# module.net
KiCad netlist of a schematic drawn in EAGLE
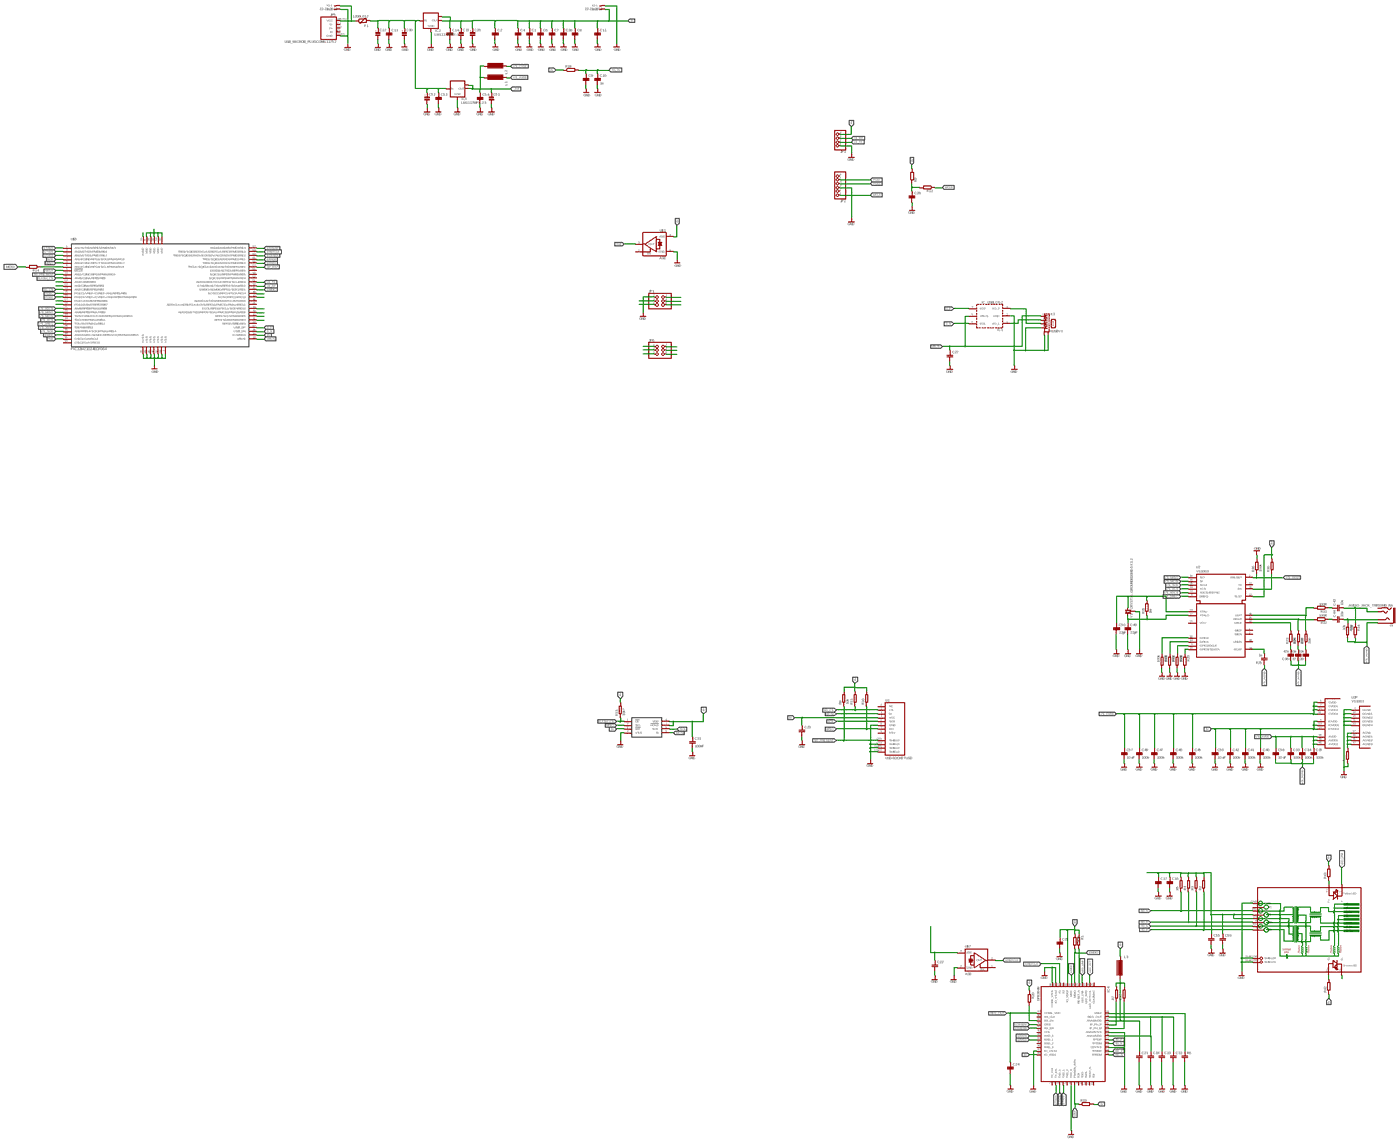
[diagram p0: schematic, sheet 1, overview]
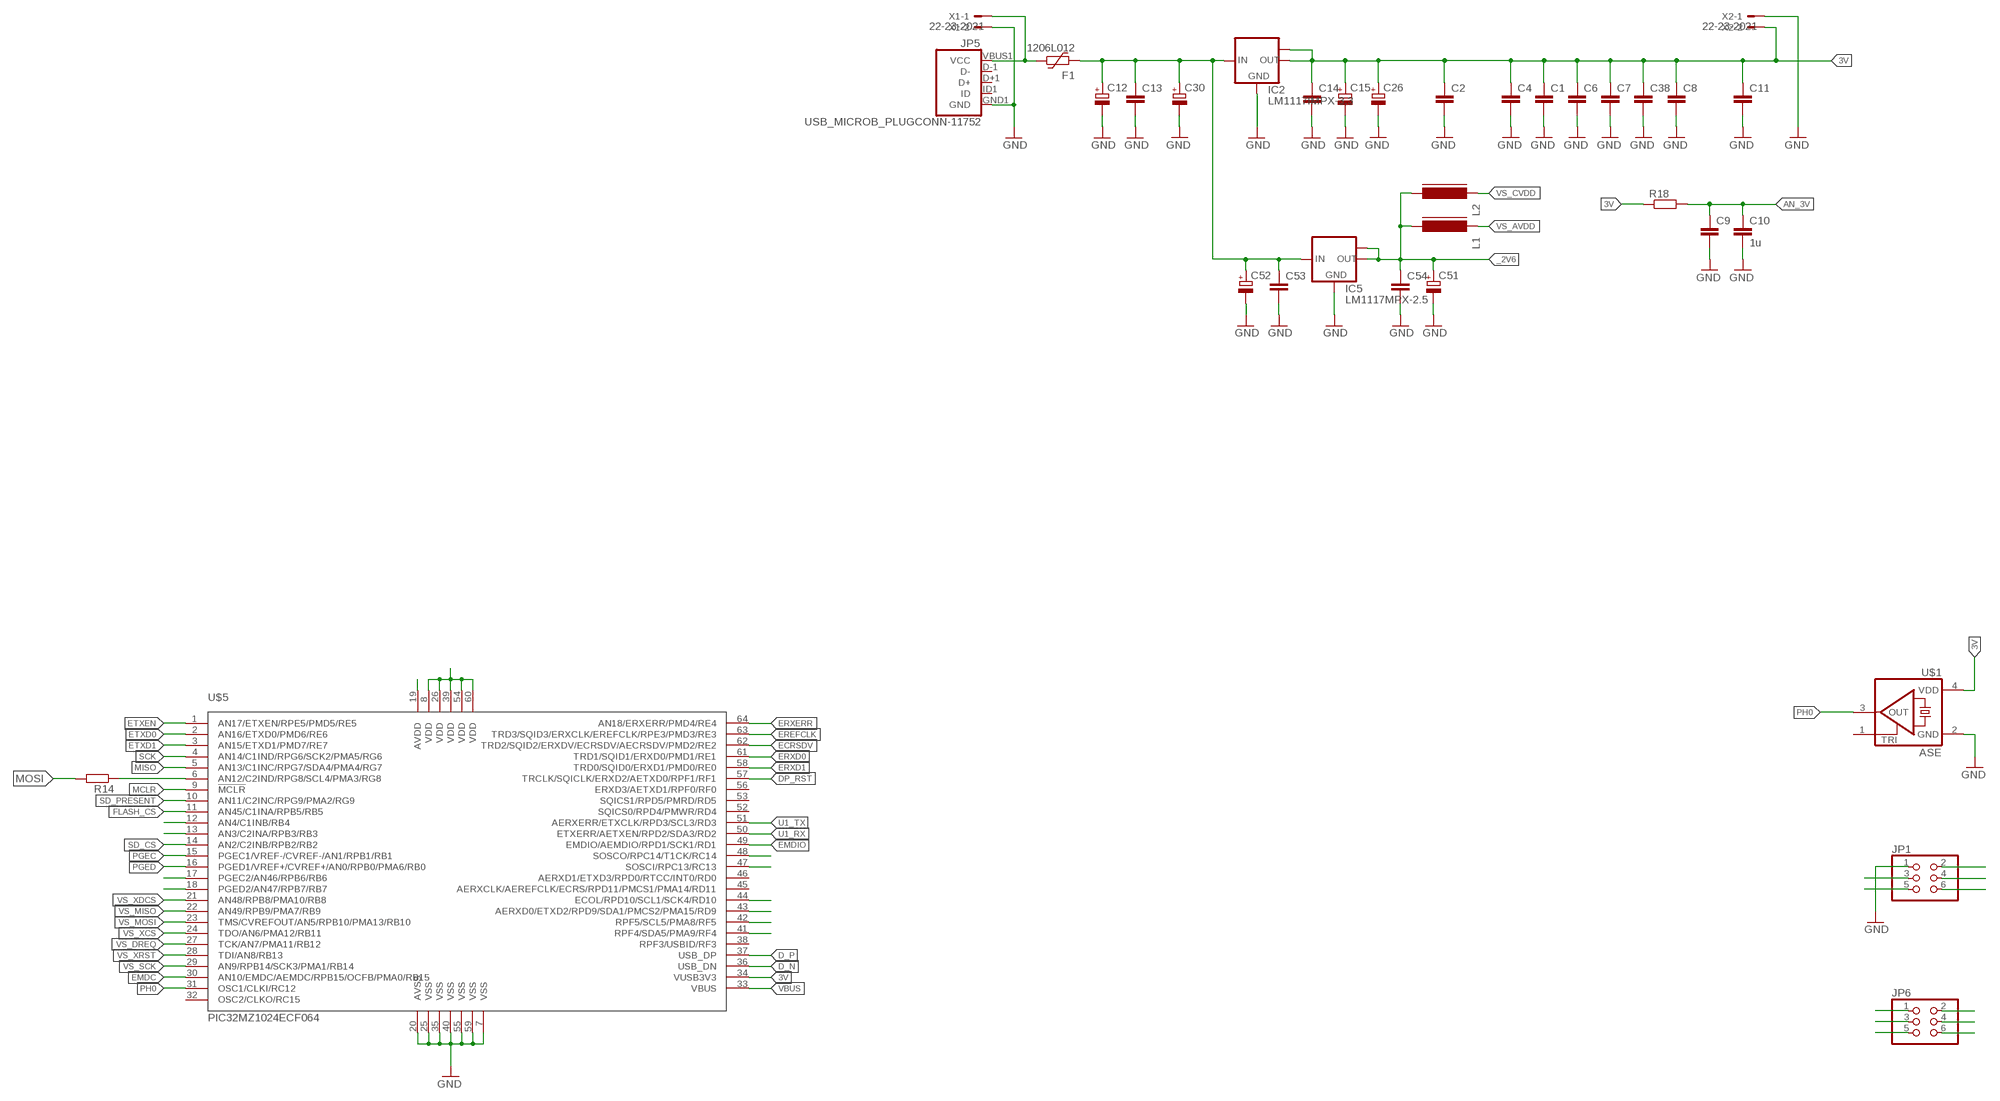
[diagram p1: schematic, sheet 1, part 1 of 4]
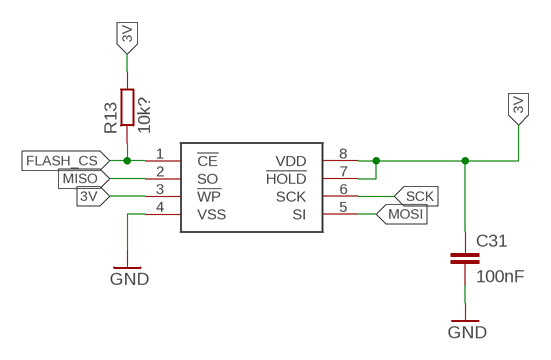
[diagram p2: schematic, sheet 1, part 2 of 4]
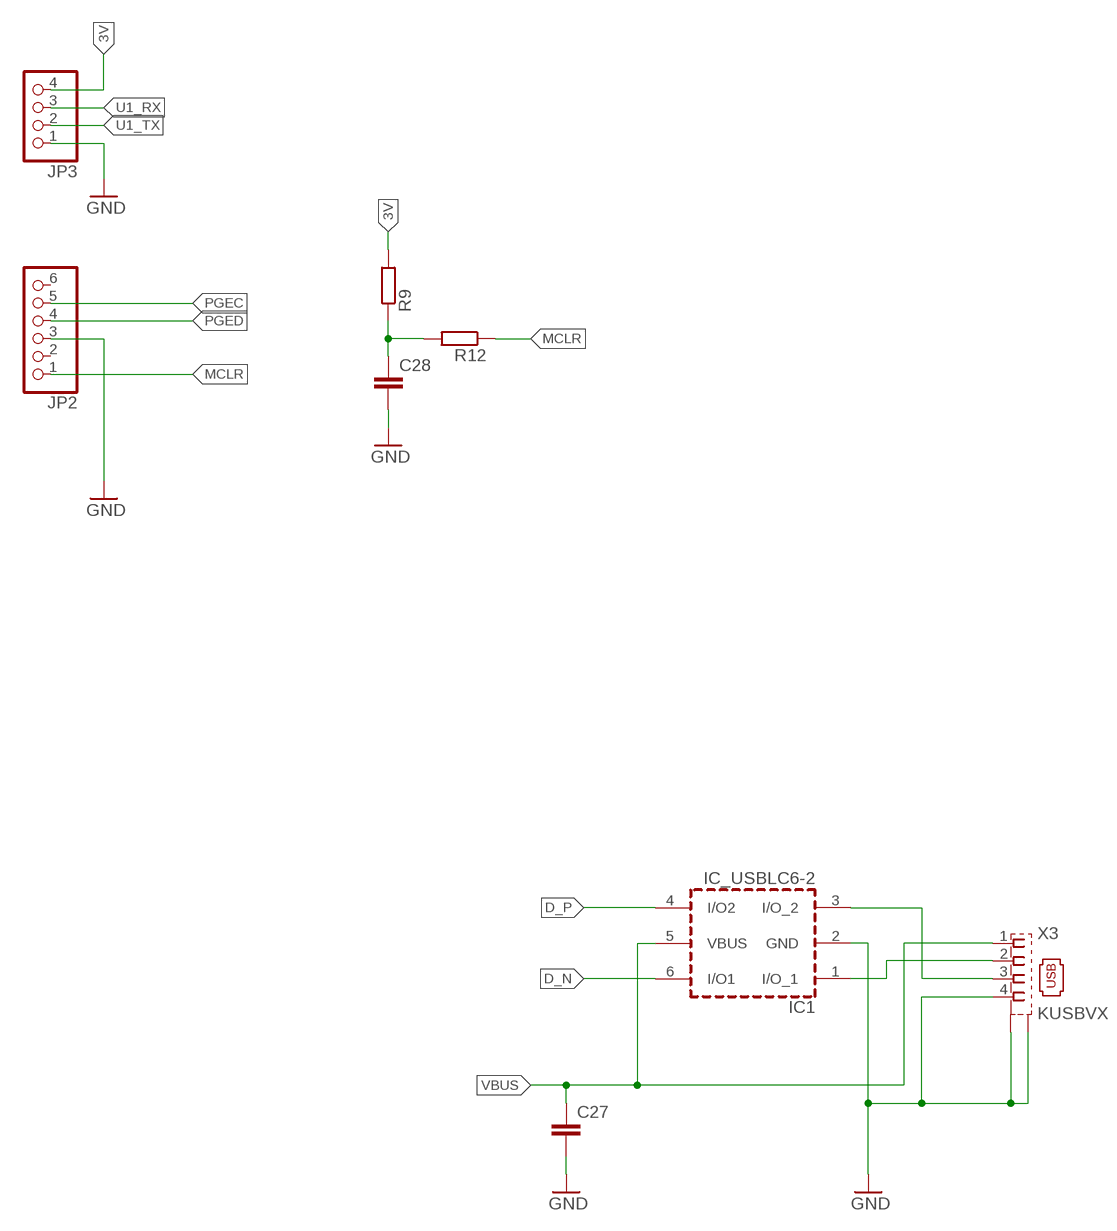
[diagram p3: schematic, sheet 1, part 3 of 4]
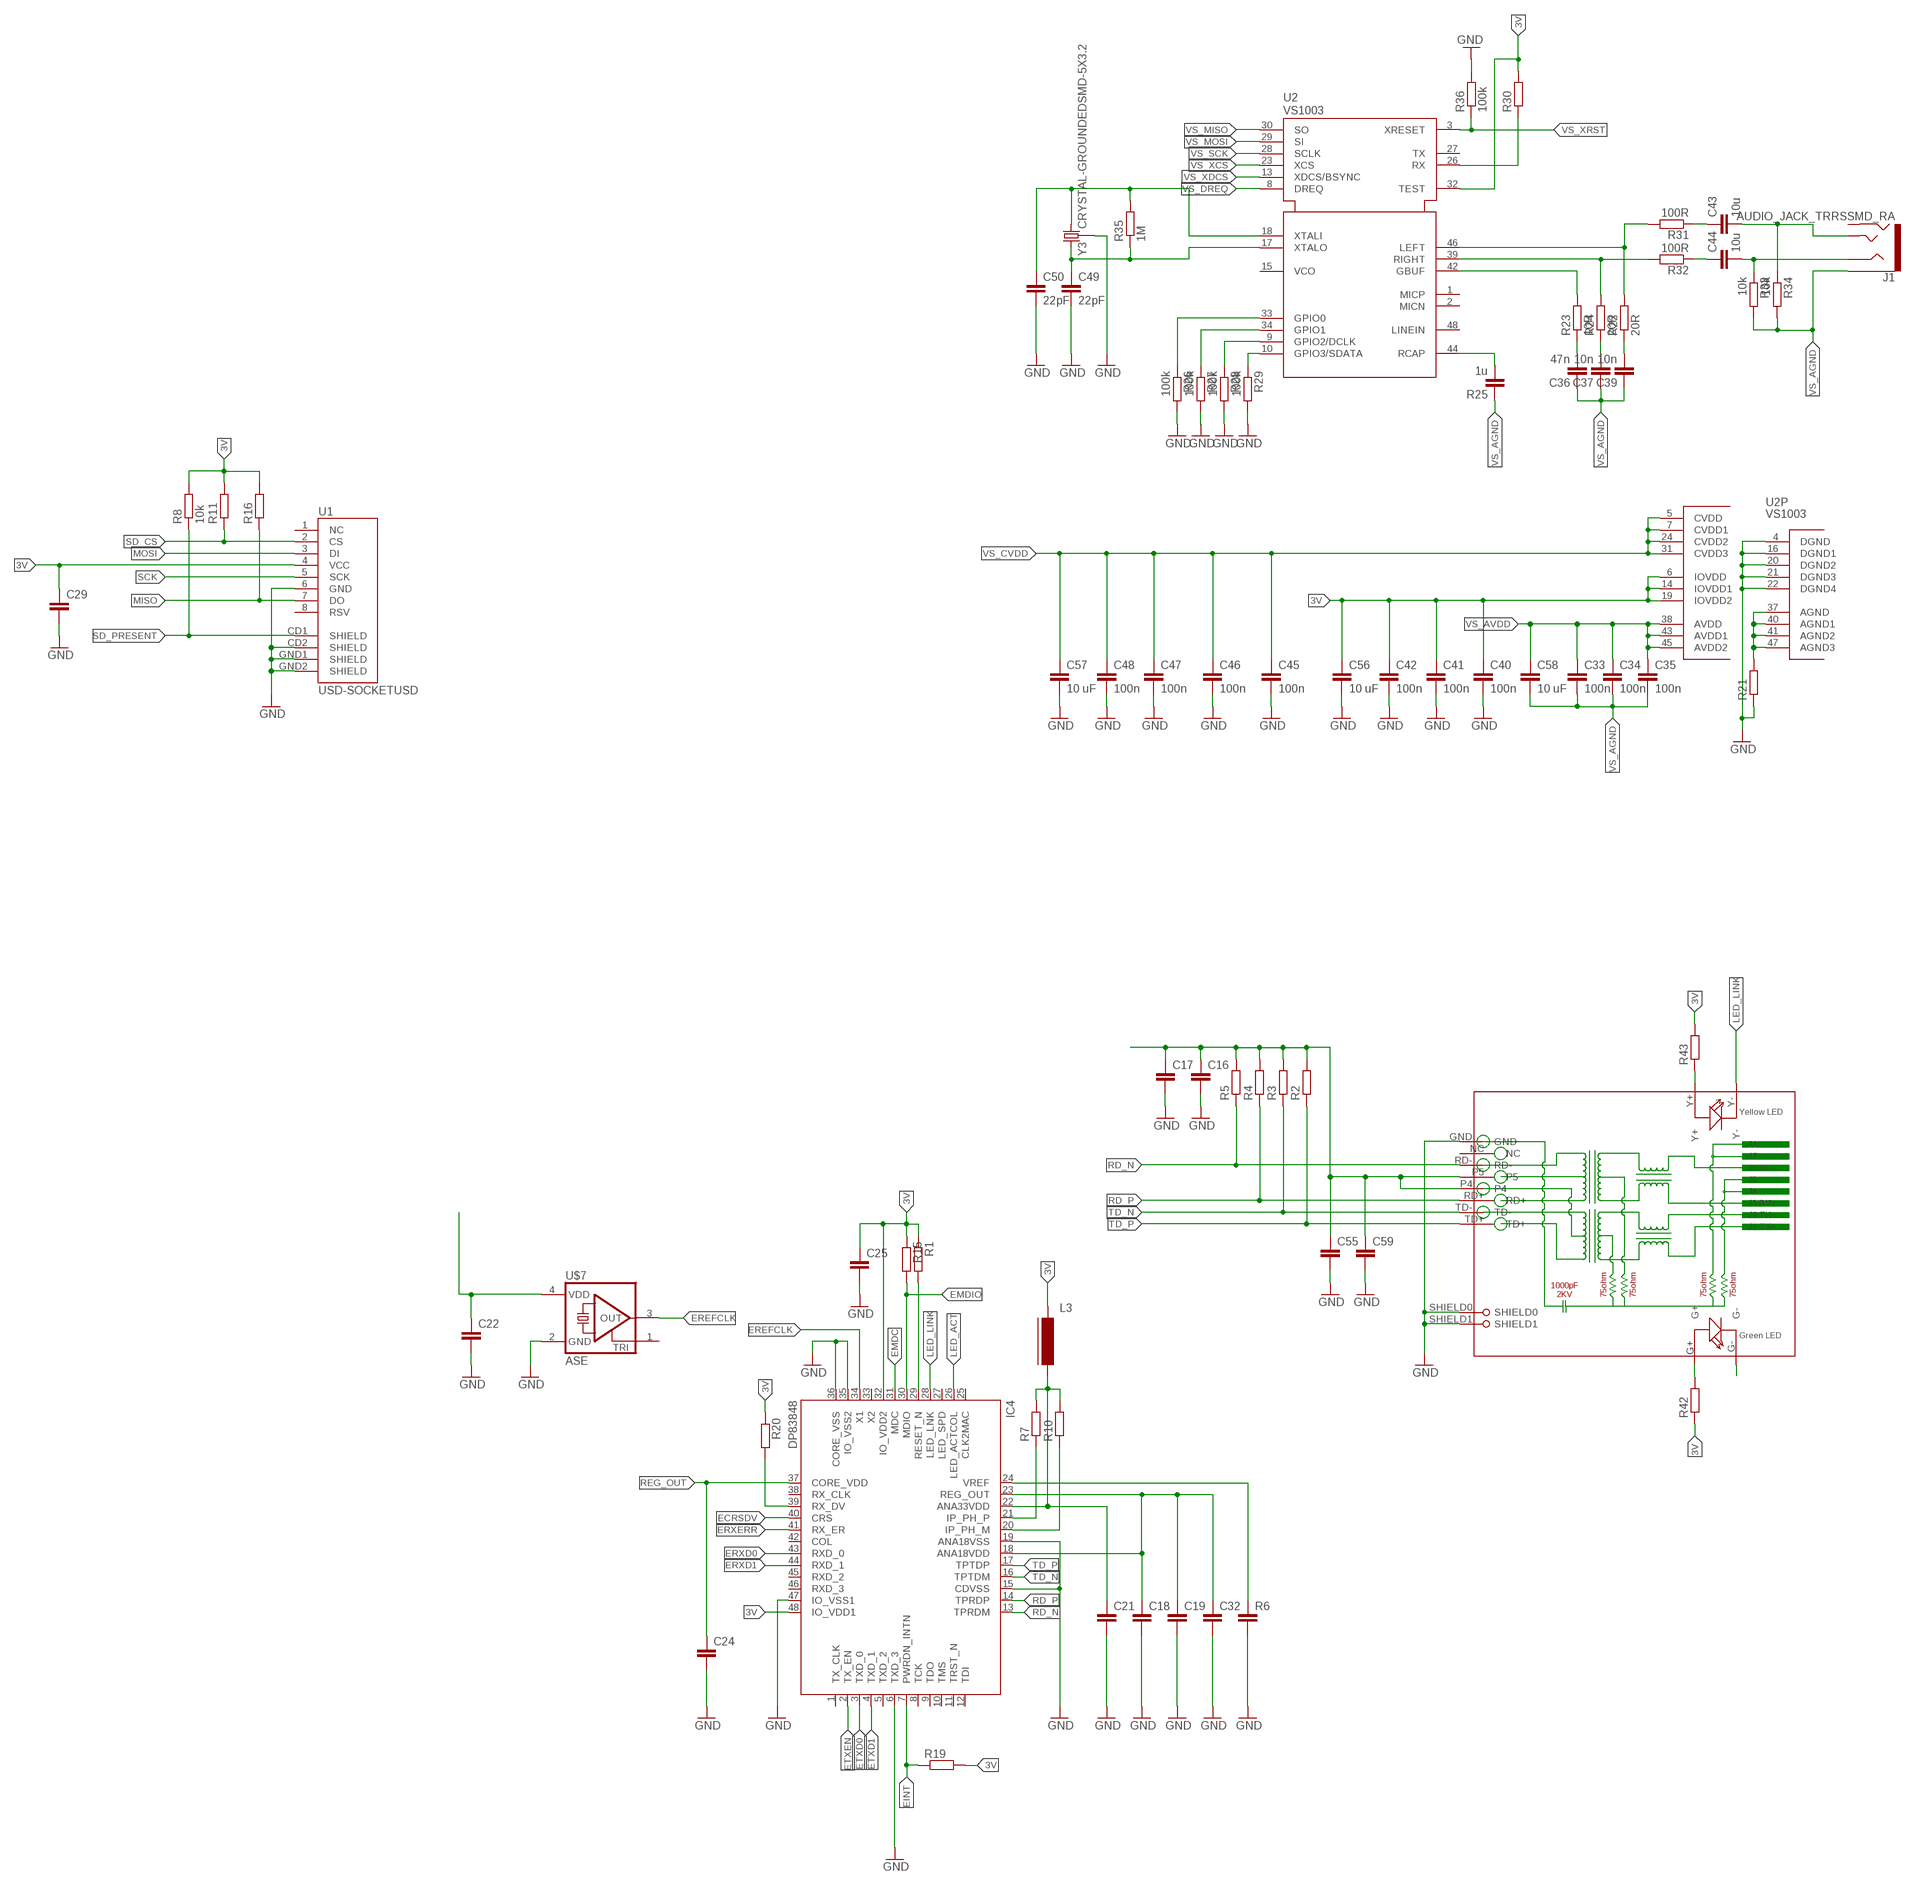
[diagram p4: schematic, sheet 1, part 4 of 4]

(export (version "E")
  (design (tool "Eeschema 10.0.6"))
  (components
    (comp (ref "C1")
      (value "C-EUC0402")
      (footprint "eagle-import:C0402")
      (libsource (lib "eagle-import") (part "C-EUC0402"))
    )
    (comp (ref "C2")
      (value "C-EUC0402")
      (footprint "eagle-import:C0402")
      (libsource (lib "eagle-import") (part "C-EUC0402"))
    )
    (comp (ref "C4")
      (value "C-EUC0402")
      (footprint "eagle-import:C0402")
      (libsource (lib "eagle-import") (part "C-EUC0402"))
    )
    (comp (ref "C6")
      (value "C-EUC0402")
      (footprint "eagle-import:C0402")
      (libsource (lib "eagle-import") (part "C-EUC0402"))
    )
    (comp (ref "C7")
      (value "C-EUC0402")
      (footprint "eagle-import:C0402")
      (libsource (lib "eagle-import") (part "C-EUC0402"))
    )
    (comp (ref "C8")
      (value "C-EUC0402")
      (footprint "eagle-import:C0402")
      (libsource (lib "eagle-import") (part "C-EUC0402"))
    )
    (comp (ref "C9")
      (value "C-EUC0402")
      (footprint "eagle-import:C0402")
      (libsource (lib "eagle-import") (part "C-EUC0402"))
    )
    (comp (ref "C10")
      (value "1u")
      (footprint "eagle-import:C0603")
      (libsource (lib "eagle-import") (part "C-EUC0603"))
    )
    (comp (ref "C11")
      (value "C-EUC0402")
      (footprint "eagle-import:C0402")
      (libsource (lib "eagle-import") (part "C-EUC0402"))
    )
    (comp (ref "C12")
      (value "CPOL-EUSMCB")
      (footprint "eagle-import:SMC_B")
      (libsource (lib "eagle-import") (part "CPOL-EUSMCB"))
    )
    (comp (ref "C13")
      (value "C-EUC0603")
      (footprint "eagle-import:C0603")
      (libsource (lib "eagle-import") (part "C-EUC0603"))
    )
    (comp (ref "C14")
      (value "C-EUC0603")
      (footprint "eagle-import:C0603")
      (libsource (lib "eagle-import") (part "C-EUC0603"))
    )
    (comp (ref "C15")
      (value "CPOL-EUSMCB")
      (footprint "eagle-import:SMC_B")
      (libsource (lib "eagle-import") (part "CPOL-EUSMCB"))
    )
    (comp (ref "C16")
      (value "C-EUC0603")
      (footprint "eagle-import:C0603")
      (libsource (lib "eagle-import") (part "C-EUC0603"))
    )
    (comp (ref "C17")
      (value "C-EUC0603")
      (footprint "eagle-import:C0603")
      (libsource (lib "eagle-import") (part "C-EUC0603"))
    )
    (comp (ref "C18")
      (value "C-EUC0402")
      (footprint "eagle-import:C0402")
      (libsource (lib "eagle-import") (part "C-EUC0402"))
    )
    (comp (ref "C19")
      (value "C-EUC0402")
      (footprint "eagle-import:C0402")
      (libsource (lib "eagle-import") (part "C-EUC0402"))
    )
    (comp (ref "C21")
      (value "C-EUC0402")
      (footprint "eagle-import:C0402")
      (libsource (lib "eagle-import") (part "C-EUC0402"))
    )
    (comp (ref "C22")
      (value "C-EUC0402")
      (footprint "eagle-import:C0402")
      (libsource (lib "eagle-import") (part "C-EUC0402"))
    )
    (comp (ref "C24")
      (value "C-EUC0603")
      (footprint "eagle-import:C0603")
      (libsource (lib "eagle-import") (part "C-EUC0603"))
    )
    (comp (ref "C25")
      (value "C-EUC0603")
      (footprint "eagle-import:C0603")
      (libsource (lib "eagle-import") (part "C-EUC0603"))
    )
    (comp (ref "C26")
      (value "CPOL-EUSMCA")
      (footprint "eagle-import:SMC_A")
      (libsource (lib "eagle-import") (part "CPOL-EUSMCA"))
    )
    (comp (ref "C27")
      (value "C-EUC0603")
      (footprint "eagle-import:C0603")
      (libsource (lib "eagle-import") (part "C-EUC0603"))
    )
    (comp (ref "C28")
      (value "C-EUC0603")
      (footprint "eagle-import:C0603")
      (libsource (lib "eagle-import") (part "C-EUC0603"))
    )
    (comp (ref "C29")
      (value "C-EUC0603")
      (footprint "eagle-import:C0603")
      (libsource (lib "eagle-import") (part "C-EUC0603"))
    )
    (comp (ref "C30")
      (value "CPOL-EUSMCA")
      (footprint "eagle-import:SMC_A")
      (libsource (lib "eagle-import") (part "CPOL-EUSMCA"))
    )
    (comp (ref "C31")
      (value "100nF")
      (footprint "eagle-import:C0603")
      (libsource (lib "eagle-import") (part "C-EUC0603"))
    )
    (comp (ref "C32")
      (value "C-EUC0603")
      (footprint "eagle-import:C0603")
      (libsource (lib "eagle-import") (part "C-EUC0603"))
    )
    (comp (ref "C33")
      (value "100n")
      (footprint "eagle-import:C0603")
      (libsource (lib "eagle-import") (part "C-EUC0603"))
    )
    (comp (ref "C34")
      (value "100n")
      (footprint "eagle-import:C0603")
      (libsource (lib "eagle-import") (part "C-EUC0603"))
    )
    (comp (ref "C35")
      (value "100n")
      (footprint "eagle-import:C0603")
      (libsource (lib "eagle-import") (part "C-EUC0603"))
    )
    (comp (ref "C36")
      (value "47n")
      (footprint "eagle-import:C0603")
      (libsource (lib "eagle-import") (part "C-EUC0603"))
    )
    (comp (ref "C37")
      (value "10n")
      (footprint "eagle-import:C0603")
      (libsource (lib "eagle-import") (part "C-EUC0603"))
    )
    (comp (ref "C38")
      (value "C-EUC0402")
      (footprint "eagle-import:C0402")
      (libsource (lib "eagle-import") (part "C-EUC0402"))
    )
    (comp (ref "C39")
      (value "10n")
      (footprint "eagle-import:C0603")
      (libsource (lib "eagle-import") (part "C-EUC0603"))
    )
    (comp (ref "C40")
      (value "100n")
      (footprint "eagle-import:C0402")
      (libsource (lib "eagle-import") (part "C-EUC0402"))
    )
    (comp (ref "C41")
      (value "100n")
      (footprint "eagle-import:C0402")
      (libsource (lib "eagle-import") (part "C-EUC0402"))
    )
    (comp (ref "C42")
      (value "100n")
      (footprint "eagle-import:C0402")
      (libsource (lib "eagle-import") (part "C-EUC0402"))
    )
    (comp (ref "C43")
      (value "10u")
      (footprint "eagle-import:C0603")
      (libsource (lib "eagle-import") (part "C-EUC0603"))
    )
    (comp (ref "C44")
      (value "10u")
      (footprint "eagle-import:C0603")
      (libsource (lib "eagle-import") (part "C-EUC0603"))
    )
    (comp (ref "C45")
      (value "100n")
      (footprint "eagle-import:C0402")
      (libsource (lib "eagle-import") (part "C-EUC0402"))
    )
    (comp (ref "C46")
      (value "100n")
      (footprint "eagle-import:C0603")
      (libsource (lib "eagle-import") (part "C-EUC0603"))
    )
    (comp (ref "C47")
      (value "100n")
      (footprint "eagle-import:C0603")
      (libsource (lib "eagle-import") (part "C-EUC0603"))
    )
    (comp (ref "C48")
      (value "100n")
      (footprint "eagle-import:C0603")
      (libsource (lib "eagle-import") (part "C-EUC0603"))
    )
    (comp (ref "C49")
      (value "22pF")
      (footprint "eagle-import:C0603")
      (libsource (lib "eagle-import") (part "C-EUC0603"))
    )
    (comp (ref "C50")
      (value "22pF")
      (footprint "eagle-import:C0603")
      (libsource (lib "eagle-import") (part "C-EUC0603"))
    )
    (comp (ref "C51")
      (value "CPOL-EUSMCB")
      (footprint "eagle-import:SMC_B")
      (libsource (lib "eagle-import") (part "CPOL-EUSMCB"))
    )
    (comp (ref "C52")
      (value "CPOL-EUSMCB")
      (footprint "eagle-import:SMC_B")
      (libsource (lib "eagle-import") (part "CPOL-EUSMCB"))
    )
    (comp (ref "C53")
      (value "C-EUC0603")
      (footprint "eagle-import:C0603")
      (libsource (lib "eagle-import") (part "C-EUC0603"))
    )
    (comp (ref "C54")
      (value "C-EUC0603")
      (footprint "eagle-import:C0603")
      (libsource (lib "eagle-import") (part "C-EUC0603"))
    )
    (comp (ref "C55")
      (value "C-EUC0603")
      (footprint "eagle-import:C0603")
      (libsource (lib "eagle-import") (part "C-EUC0603"))
    )
    (comp (ref "C56")
      (value "10 uF")
      (footprint "eagle-import:C0603")
      (libsource (lib "eagle-import") (part "C-EUC0603"))
    )
    (comp (ref "C57")
      (value "10 uF")
      (footprint "eagle-import:C0603")
      (libsource (lib "eagle-import") (part "C-EUC0603"))
    )
    (comp (ref "C58")
      (value "10 uF")
      (footprint "eagle-import:C0603")
      (libsource (lib "eagle-import") (part "C-EUC0603"))
    )
    (comp (ref "C59")
      (value "C-EUC0603")
      (footprint "eagle-import:C0603")
      (libsource (lib "eagle-import") (part "C-EUC0603"))
    )
    (comp (ref "F1")
      (value "1206L012")
      (footprint "eagle-import:1206L")
      (fields (field (name "MF") "Littelfuse"))
      (libsource (lib "eagle-import") (part "?1206L012"))
    )
    (comp (ref "IC1")
      (value "IC_USBLC6-2")
      (footprint "eagle-import:SOT-23-6L")
      (libsource (lib "eagle-import") (part "IC_USBLC6-2"))
    )
    (comp (ref "IC2")
      (value "LM1117IMPX-3.3")
      (footprint "eagle-import:SOT223")
      (libsource (lib "eagle-import") (part "LM1117IMPX-3.3"))
    )
    (comp (ref "IC4")
      (value "DP83848")
      (footprint "eagle-import:LQFP48")
      (fields (field (name "MPN") "DP83848VYB"))
      (libsource (lib "eagle-import") (part "DP83848"))
    )
    (comp (ref "IC5")
      (value "LM1117MPX-2.5")
      (footprint "eagle-import:SOT223")
      (libsource (lib "eagle-import") (part "LM1117MPX-2.5"))
    )
    (comp (ref "J1")
      (value "AUDIO_JACK_TRRSSMD_RA")
      (footprint "eagle-import:AUDIO_JACK_3.5MM_TRRS_SMD_RA")
      (libsource (lib "eagle-import") (part "AUDIO_JACK_TRRSSMD_RA"))
    )
    (comp (ref "JP1")
      (value "PINHD-2X3")
      (footprint "eagle-import:2X03")
      (libsource (lib "eagle-import") (part "PINHD-2X3"))
    )
    (comp (ref "JP2")
      (value "PINHD-1X6")
      (footprint "eagle-import:1X06")
      (libsource (lib "eagle-import") (part "PINHD-1X6"))
    )
    (comp (ref "JP3")
      (value "PINHD-1X4")
      (footprint "eagle-import:1X04")
      (libsource (lib "eagle-import") (part "PINHD-1X4"))
    )
    (comp (ref "JP5")
      (value "USB_MICROB_PLUGCONN-11752")
      (footprint "eagle-import:USB-B-MICRO-SMD_V03")
      (libsource (lib "eagle-import") (part "USB_MICROB_PLUGCONN-11752"))
    )
    (comp (ref "JP6")
      (value "PINHD-2X3")
      (footprint "eagle-import:2X03")
      (libsource (lib "eagle-import") (part "PINHD-2X3"))
    )
    (comp (ref "L1")
      (value "FERRITE-0805")
      (footprint "eagle-import:FB805")
      (libsource (lib "eagle-import") (part "FERRITE-0805"))
    )
    (comp (ref "L2")
      (value "FERRITE-0805")
      (footprint "eagle-import:FB805")
      (libsource (lib "eagle-import") (part "FERRITE-0805"))
    )
    (comp (ref "L3")
      (value "FERRITE-0805")
      (footprint "eagle-import:FB805")
      (libsource (lib "eagle-import") (part "FERRITE-0805"))
    )
    (comp (ref "R1")
      (value "R-EU_R0402")
      (footprint "eagle-import:R0402")
      (libsource (lib "eagle-import") (part "R-EU_R0402"))
    )
    (comp (ref "R2")
      (value "R-EU_R0603")
      (footprint "eagle-import:R0603")
      (libsource (lib "eagle-import") (part "R-EU_R0603"))
    )
    (comp (ref "R3")
      (value "R-EU_R0603")
      (footprint "eagle-import:R0603")
      (libsource (lib "eagle-import") (part "R-EU_R0603"))
    )
    (comp (ref "R4")
      (value "R-EU_R0603")
      (footprint "eagle-import:R0603")
      (libsource (lib "eagle-import") (part "R-EU_R0603"))
    )
    (comp (ref "R5")
      (value "R-EU_R0603")
      (footprint "eagle-import:R0603")
      (libsource (lib "eagle-import") (part "R-EU_R0603"))
    )
    (comp (ref "R6")
      (value "C-EUC0603")
      (footprint "eagle-import:C0603")
      (libsource (lib "eagle-import") (part "C-EUC0603"))
    )
    (comp (ref "R7")
      (value "R-EU_R0402")
      (footprint "eagle-import:R0402")
      (libsource (lib "eagle-import") (part "R-EU_R0402"))
    )
    (comp (ref "R8")
      (value "10k")
      (footprint "eagle-import:R0603")
      (libsource (lib "eagle-import") (part "R-EU_R0603"))
    )
    (comp (ref "R9")
      (value "R-EU_R0603")
      (footprint "eagle-import:R0603")
      (libsource (lib "eagle-import") (part "R-EU_R0603"))
    )
    (comp (ref "R10")
      (value "R-EU_R0402")
      (footprint "eagle-import:R0402")
      (libsource (lib "eagle-import") (part "R-EU_R0402"))
    )
    (comp (ref "R11")
      (value "R-EU_R0603")
      (footprint "eagle-import:R0603")
      (libsource (lib "eagle-import") (part "R-EU_R0603"))
    )
    (comp (ref "R12")
      (value "R-EU_R0402")
      (footprint "eagle-import:R0402")
      (libsource (lib "eagle-import") (part "R-EU_R0402"))
    )
    (comp (ref "R13")
      (value "10k?")
      (footprint "eagle-import:R0603")
      (libsource (lib "eagle-import") (part "R-EU_R0603"))
    )
    (comp (ref "R14")
      (value "R-EU_R0603")
      (footprint "eagle-import:R0603")
      (libsource (lib "eagle-import") (part "R-EU_R0603"))
    )
    (comp (ref "R15")
      (value "R-EU_R0603")
      (footprint "eagle-import:R0603")
      (libsource (lib "eagle-import") (part "R-EU_R0603"))
    )
    (comp (ref "R16")
      (value "R-EU_R0603")
      (footprint "eagle-import:R0603")
      (libsource (lib "eagle-import") (part "R-EU_R0603"))
    )
    (comp (ref "R18")
      (value "R-EU_R0805")
      (footprint "eagle-import:R0805")
      (libsource (lib "eagle-import") (part "R-EU_R0805"))
    )
    (comp (ref "R19")
      (value "R-EU_R0402")
      (footprint "eagle-import:R0402")
      (libsource (lib "eagle-import") (part "R-EU_R0402"))
    )
    (comp (ref "R20")
      (value "R-EU_R0603")
      (footprint "eagle-import:R0603")
      (libsource (lib "eagle-import") (part "R-EU_R0603"))
    )
    (comp (ref "R21")
      (value "R-EU_R0603")
      (footprint "eagle-import:R0603")
      (libsource (lib "eagle-import") (part "R-EU_R0603"))
    )
    (comp (ref "R22")
      (value "20R")
      (footprint "eagle-import:R0603")
      (libsource (lib "eagle-import") (part "R-EU_R0603"))
    )
    (comp (ref "R23")
      (value "10R")
      (footprint "eagle-import:R0603")
      (libsource (lib "eagle-import") (part "R-EU_R0603"))
    )
    (comp (ref "R24")
      (value "20R")
      (footprint "eagle-import:R0603")
      (libsource (lib "eagle-import") (part "R-EU_R0603"))
    )
    (comp (ref "R25")
      (value "1u")
      (footprint "eagle-import:C0603")
      (libsource (lib "eagle-import") (part "C-EUC0603"))
    )
    (comp (ref "R26")
      (value "100k")
      (footprint "eagle-import:R0402")
      (libsource (lib "eagle-import") (part "R-EU_R0402"))
    )
    (comp (ref "R27")
      (value "100k")
      (footprint "eagle-import:R0402")
      (libsource (lib "eagle-import") (part "R-EU_R0402"))
    )
    (comp (ref "R28")
      (value "100k")
      (footprint "eagle-import:R0402")
      (libsource (lib "eagle-import") (part "R-EU_R0402"))
    )
    (comp (ref "R29")
      (value "100k")
      (footprint "eagle-import:R0402")
      (libsource (lib "eagle-import") (part "R-EU_R0402"))
    )
    (comp (ref "R30")
      (value "R-EU_0204/7")
      (footprint "eagle-import:0204_7")
      (libsource (lib "eagle-import") (part "R-EU_0204/7"))
    )
    (comp (ref "R31")
      (value "100R")
      (footprint "eagle-import:R0603")
      (libsource (lib "eagle-import") (part "R-EU_R0603"))
    )
    (comp (ref "R32")
      (value "100R")
      (footprint "eagle-import:R0603")
      (libsource (lib "eagle-import") (part "R-EU_R0603"))
    )
    (comp (ref "R33")
      (value "10k")
      (footprint "eagle-import:R0603")
      (libsource (lib "eagle-import") (part "R-EU_R0603"))
    )
    (comp (ref "R34")
      (value "10k")
      (footprint "eagle-import:R0603")
      (libsource (lib "eagle-import") (part "R-EU_R0603"))
    )
    (comp (ref "R35")
      (value "1M")
      (footprint "eagle-import:R0603")
      (libsource (lib "eagle-import") (part "R-EU_R0603"))
    )
    (comp (ref "R36")
      (value "100k")
      (footprint "eagle-import:R0603")
      (libsource (lib "eagle-import") (part "R-EU_R0603"))
    )
    (comp (ref "R42")
      (value "R-EU_R0603")
      (footprint "eagle-import:R0603")
      (libsource (lib "eagle-import") (part "R-EU_R0603"))
    )
    (comp (ref "R43")
      (value "R-EU_R0603")
      (footprint "eagle-import:R0603")
      (libsource (lib "eagle-import") (part "R-EU_R0603"))
    )
    (comp (ref "RJ1")
      (value "HR911105A")
      (footprint "eagle-import:HR911105A")
      (libsource (lib "eagle-import") (part "HR911105A"))
    )
    (comp (ref "U$1")
      (value "ASE")
      (footprint "eagle-import:ASE")
      (libsource (lib "eagle-import") (part "ASE"))
    )
    (comp (ref "U$2")
      (value "SST25VF016BSO8M")
      (footprint "eagle-import:SO-08M")
      (libsource (lib "eagle-import") (part "SST25VF016BSO8M"))
    )
    (comp (ref "U$5")
      (value "PIC32MZ1024ECF064")
      (footprint "eagle-import:TQFP64-10X10")
      (libsource (lib "eagle-import") (part "PIC32MZ1024ECF064"))
    )
    (comp (ref "U$7")
      (value "ASE")
      (footprint "eagle-import:ASE")
      (libsource (lib "eagle-import") (part "ASE"))
    )
    (comp (ref "U1")
      (value "USD-SOCKETUSD")
      (footprint "eagle-import:USD-SOCKET-PP")
      (libsource (lib "eagle-import") (part "USD-SOCKETUSD"))
    )
    (comp (ref "U2")
      (value "VS1003")
      (footprint "eagle-import:LQFP48")
      (libsource (lib "eagle-import") (part "VS1003"))
    )
    (comp (ref "X1")
      (value "22-23-2021")
      (footprint "eagle-import:22-23-2021")
      (fields (field (name "MF") "MOLEX"))
      (libsource (lib "eagle-import") (part "22-23-2021"))
    )
    (comp (ref "X2")
      (value "22-23-2021")
      (footprint "eagle-import:22-23-2021")
      (fields (field (name "MF") "MOLEX"))
      (libsource (lib "eagle-import") (part "22-23-2021"))
    )
    (comp (ref "X3")
      (value "KUSBVX")
      (footprint "eagle-import:KUSBVX")
      (libsource (lib "eagle-import") (part "KUSBVX"))
    )
    (comp (ref "Y3")
      (value "CRYSTAL-GROUNDEDSMD-5X3.2")
      (footprint "eagle-import:CRYSTAL-SMD-5X3.2-4PAD")
      (libsource (lib "eagle-import") (part "CRYSTAL-GROUNDEDSMD-5X3.2"))
    )
  )
  (nets
    (net (code "1") (name "/A3V") (class "Default")
      (node (ref "C16") (pin "1") (pinfunction "1_1") (pintype "passive"))
      (node (ref "C17") (pin "1") (pinfunction "1_1") (pintype "passive"))
      (node (ref "C21") (pin "1") (pinfunction "1_1") (pintype "passive"))
      (node (ref "C55") (pin "1") (pinfunction "1_1") (pintype "passive"))
      (node (ref "C59") (pin "1") (pinfunction "1_1") (pintype "passive"))
      (node (ref "IC4") (pin "22") (pinfunction "ANA33VDD_22") (pintype "power_in"))
      (node (ref "L3") (pin "2") (pinfunction "2_2") (pintype "passive"))
      (node (ref "R10") (pin "2") (pinfunction "2_2") (pintype "passive"))
      (node (ref "R2") (pin "2") (pinfunction "2_2") (pintype "passive"))
      (node (ref "R3") (pin "2") (pinfunction "2_2") (pintype "passive"))
      (node (ref "R4") (pin "2") (pinfunction "2_2") (pintype "passive"))
      (node (ref "R5") (pin "2") (pinfunction "2_2") (pintype "passive"))
      (node (ref "R7") (pin "2") (pinfunction "2_2") (pintype "passive"))
      (node (ref "RJ1") (pin "P4") (pinfunction "P4_P4") (pintype "bidirectional"))
      (node (ref "RJ1") (pin "P5") (pinfunction "P5_P5") (pintype "bidirectional"))
    )
    (net (code "2") (name "/RB3") (class "Default")
      (node (ref "JP1") (pin "5") (pinfunction "5_5") (pintype "passive"))
      (node (ref "U$5") (pin "13") (pinfunction "AN3/C2INA/RPB3/RB3_13") (pintype "bidirectional"))
    )
    (net (code "3") (name "/RB4") (class "Default")
      (node (ref "JP1") (pin "3") (pinfunction "3_3") (pintype "passive"))
      (node (ref "U$5") (pin "12") (pinfunction "AN4/C1INB/RB4_12") (pintype "bidirectional"))
    )
    (net (code "4") (name "/RB6") (class "Default")
      (node (ref "JP1") (pin "6") (pinfunction "6_6") (pintype "passive"))
      (node (ref "U$5") (pin "17") (pinfunction "PGEC2/AN46/RPB6/RB6_17") (pintype "bidirectional"))
    )
    (net (code "5") (name "/RB7") (class "Default")
      (node (ref "JP1") (pin "4") (pinfunction "4_4") (pintype "passive"))
      (node (ref "U$5") (pin "18") (pinfunction "PGED2/AN47/RPB7/RB7_18") (pintype "bidirectional"))
    )
    (net (code "6") (name "/RC13") (class "Default")
      (node (ref "JP6") (pin "5") (pinfunction "5_5") (pintype "passive"))
      (node (ref "U$5") (pin "47") (pinfunction "SOSCI/RPC13/RC13_47") (pintype "bidirectional"))
    )
    (net (code "7") (name "/RC14") (class "Default")
      (node (ref "JP6") (pin "6") (pinfunction "6_6") (pintype "passive"))
      (node (ref "U$5") (pin "48") (pinfunction "SOSCO/RPC14/T1CK/RC14_48") (pintype "bidirectional"))
    )
    (net (code "8") (name "/SCL1") (class "Default")
      (node (ref "JP6") (pin "4") (pinfunction "4_4") (pintype "passive"))
      (node (ref "U$5") (pin "44") (pinfunction "ECOL/RPD10/SCL1/SCK4/RD10_44") (pintype "bidirectional"))
    )
    (net (code "9") (name "/SCL5") (class "Default")
      (node (ref "JP6") (pin "2") (pinfunction "2_2") (pintype "passive"))
      (node (ref "U$5") (pin "42") (pinfunction "RPF5/SCL5/PMA8/RF5_42") (pintype "bidirectional"))
    )
    (net (code "10") (name "/SDA1") (class "Default")
      (node (ref "JP6") (pin "3") (pinfunction "3_3") (pintype "passive"))
      (node (ref "U$5") (pin "43") (pinfunction "AERXD0/ETXD2/RPD9/SDA1/PMCS2/PMA15/RD9_43") (pintype "bidirectional"))
    )
    (net (code "11") (name "/SDA5") (class "Default")
      (node (ref "JP6") (pin "1") (pinfunction "1_1") (pintype "passive"))
      (node (ref "U$5") (pin "41") (pinfunction "RPF4/SDA5/PMA9/RF4_41") (pintype "bidirectional"))
    )
    (net (code "12") (name "3V") (class "Default")
      (node (ref "C1") (pin "1") (pinfunction "1_1") (pintype "passive"))
      (node (ref "C11") (pin "1") (pinfunction "1_1") (pintype "passive"))
      (node (ref "C14") (pin "1") (pinfunction "1_1") (pintype "passive"))
      (node (ref "C15") (pin "+") (pinfunction "+_+") (pintype "passive"))
      (node (ref "C2") (pin "1") (pinfunction "1_1") (pintype "passive"))
      (node (ref "C22") (pin "1") (pinfunction "1_1") (pintype "passive"))
      (node (ref "C25") (pin "1") (pinfunction "1_1") (pintype "passive"))
      (node (ref "C26") (pin "+") (pinfunction "+_+") (pintype "passive"))
      (node (ref "C29") (pin "1") (pinfunction "1_1") (pintype "passive"))
      (node (ref "C31") (pin "1") (pinfunction "1_1") (pintype "passive"))
      (node (ref "C38") (pin "1") (pinfunction "1_1") (pintype "passive"))
      (node (ref "C4") (pin "1") (pinfunction "1_1") (pintype "passive"))
      (node (ref "C40") (pin "1") (pinfunction "1_1") (pintype "passive"))
      (node (ref "C41") (pin "1") (pinfunction "1_1") (pintype "passive"))
      (node (ref "C42") (pin "1") (pinfunction "1_1") (pintype "passive"))
      (node (ref "C56") (pin "1") (pinfunction "1_1") (pintype "passive"))
      (node (ref "C6") (pin "1") (pinfunction "1_1") (pintype "passive"))
      (node (ref "C7") (pin "1") (pinfunction "1_1") (pintype "passive"))
      (node (ref "C8") (pin "1") (pinfunction "1_1") (pintype "passive"))
      (node (ref "IC2") (pin "2") (pinfunction "OUT_2") (pintype "passive"))
      (node (ref "IC2") (pin "TAB") (pinfunction "OUT1_TAB") (pintype "passive"))
      (node (ref "IC4") (pin "32") (pinfunction "IO_VDD2_32") (pintype "power_in"))
      (node (ref "IC4") (pin "48") (pinfunction "IO_VDD1_48") (pintype "power_in"))
      (node (ref "JP1") (pin "2") (pinfunction "2_2") (pintype "passive"))
      (node (ref "JP3") (pin "4") (pinfunction "4_4") (pintype "passive"))
      (node (ref "L3") (pin "1") (pinfunction "1_1") (pintype "passive"))
      (node (ref "R1") (pin "1") (pinfunction "1_1") (pintype "passive"))
      (node (ref "R11") (pin "2") (pinfunction "2_2") (pintype "passive"))
      (node (ref "R13") (pin "2") (pinfunction "2_2") (pintype "passive"))
      (node (ref "R15") (pin "1") (pinfunction "1_1") (pintype "passive"))
      (node (ref "R16") (pin "2") (pinfunction "2_2") (pintype "passive"))
      (node (ref "R18") (pin "1") (pinfunction "1_1") (pintype "passive"))
      (node (ref "R19") (pin "2") (pinfunction "2_2") (pintype "passive"))
      (node (ref "R20") (pin "1") (pinfunction "1_1") (pintype "passive"))
      (node (ref "R30") (pin "2") (pinfunction "2_2") (pintype "passive"))
      (node (ref "R42") (pin "1") (pinfunction "1_1") (pintype "passive"))
      (node (ref "R43") (pin "2") (pinfunction "2_2") (pintype "passive"))
      (node (ref "R8") (pin "2") (pinfunction "2_2") (pintype "passive"))
      (node (ref "R9") (pin "2") (pinfunction "2_2") (pintype "passive"))
      (node (ref "U$1") (pin "4") (pinfunction "VDD_4") (pintype "power_in"))
      (node (ref "U$2") (pin "3") (pinfunction "~{WP}_3") (pintype "bidirectional"))
      (node (ref "U$2") (pin "7") (pinfunction "~{HOLD}_7") (pintype "bidirectional"))
      (node (ref "U$2") (pin "8") (pinfunction "VDD_8") (pintype "bidirectional"))
      (node (ref "U$5") (pin "26") (pinfunction "VDD_26") (pintype "bidirectional"))
      (node (ref "U$5") (pin "34") (pinfunction "VUSB3V3_34") (pintype "bidirectional"))
      (node (ref "U$5") (pin "39") (pinfunction "VDD_39") (pintype "bidirectional"))
      (node (ref "U$5") (pin "54") (pinfunction "VDD_54") (pintype "bidirectional"))
      (node (ref "U$5") (pin "60") (pinfunction "VDD_60") (pintype "bidirectional"))
      (node (ref "U$5") (pin "8") (pinfunction "VDD_8") (pintype "bidirectional"))
      (node (ref "U$7") (pin "4") (pinfunction "VDD_4") (pintype "power_in"))
      (node (ref "U1") (pin "4") (pinfunction "VCC_4") (pintype "bidirectional"))
      (node (ref "U2") (pin "14") (pinfunction "IOVDD1_14") (pintype "power_in"))
      (node (ref "U2") (pin "19") (pinfunction "IOVDD2_19") (pintype "power_in"))
      (node (ref "U2") (pin "32") (pinfunction "TEST_32") (pintype "bidirectional"))
      (node (ref "U2") (pin "6") (pinfunction "IOVDD_6") (pintype "power_in"))
      (node (ref "X2") (pin "2") (pinfunction "S_2") (pintype "passive"))
    )
    (net (code "13") (name "AN_3V") (class "Default")
      (node (ref "C10") (pin "1") (pinfunction "1_1") (pintype "passive"))
      (node (ref "C9") (pin "1") (pinfunction "1_1") (pintype "passive"))
      (node (ref "R18") (pin "2") (pinfunction "2_2") (pintype "passive"))
      (node (ref "U$5") (pin "19") (pinfunction "AVDD_19") (pintype "bidirectional"))
    )
    (net (code "14") (name "DP_RST") (class "Default")
      (node (ref "IC4") (pin "29") (pinfunction "RESET_N_29") (pintype "input"))
      (node (ref "R1") (pin "2") (pinfunction "2_2") (pintype "passive"))
      (node (ref "U$5") (pin "57") (pinfunction "TRCLK/SQICLK/ERXD2/AETXD0/RPF1/RF1_57") (pintype "bidirectional"))
    )
    (net (code "15") (name "D_N") (class "Default")
      (node (ref "IC1") (pin "6") (pinfunction "I/O1_6") (pintype "bidirectional"))
      (node (ref "U$5") (pin "36") (pinfunction "USB_DN_36") (pintype "bidirectional"))
    )
    (net (code "16") (name "D_P") (class "Default")
      (node (ref "IC1") (pin "4") (pinfunction "I/O2_4") (pintype "bidirectional"))
      (node (ref "U$5") (pin "37") (pinfunction "USB_DP_37") (pintype "bidirectional"))
    )
    (net (code "17") (name "ECRSDV") (class "Default")
      (node (ref "IC4") (pin "40") (pinfunction "CRS_40") (pintype "bidirectional"))
      (node (ref "U$5") (pin "62") (pinfunction "TRD2/SQID2/ERXDV/ECRSDV/AECRSDV/PMD2/RE2_62") (pintype "bidirectional"))
    )
    (net (code "18") (name "EINT") (class "Default")
      (node (ref "IC4") (pin "7") (pinfunction "PWRDN_INTN_7") (pintype "bidirectional"))
      (node (ref "R19") (pin "1") (pinfunction "1_1") (pintype "passive"))
    )
    (net (code "19") (name "EMDC") (class "Default")
      (node (ref "IC4") (pin "31") (pinfunction "MDC_31") (pintype "input"))
      (node (ref "U$5") (pin "30") (pinfunction "AN10/EMDC/AEMDC/RPB15/OCFB/PMA0/RB15_30") (pintype "bidirectional"))
    )
    (net (code "20") (name "EMDIO") (class "Default")
      (node (ref "IC4") (pin "30") (pinfunction "MDIO_30") (pintype "bidirectional"))
      (node (ref "R15") (pin "2") (pinfunction "2_2") (pintype "passive"))
      (node (ref "U$5") (pin "49") (pinfunction "EMDIO/AEMDIO/RPD1/SCK1/RD1_49") (pintype "bidirectional"))
    )
    (net (code "21") (name "EREFCLK") (class "Default")
      (node (ref "IC4") (pin "34") (pinfunction "X1_34") (pintype "input"))
      (node (ref "U$5") (pin "63") (pinfunction "TRD3/SQID3/ERXCLK/EREFCLK/RPE3/PMD3/RE3_63") (pintype "bidirectional"))
      (node (ref "U$7") (pin "3") (pinfunction "OUT_3") (pintype "output"))
    )
    (net (code "22") (name "ERXD0") (class "Default")
      (node (ref "IC4") (pin "43") (pinfunction "RXD_0_43") (pintype "bidirectional"))
      (node (ref "U$5") (pin "61") (pinfunction "TRD1/SQID1/ERXD0/PMD1/RE1_61") (pintype "bidirectional"))
    )
    (net (code "23") (name "ERXD1") (class "Default")
      (node (ref "IC4") (pin "44") (pinfunction "RXD_1_44") (pintype "bidirectional"))
      (node (ref "U$5") (pin "58") (pinfunction "TRD0/SQID0/ERXD1/PMD0/RE0_58") (pintype "bidirectional"))
    )
    (net (code "24") (name "ERXERR") (class "Default")
      (node (ref "IC4") (pin "41") (pinfunction "RX_ER_41") (pintype "bidirectional"))
      (node (ref "U$5") (pin "64") (pinfunction "AN18/ERXERR/PMD4/RE4_64") (pintype "bidirectional"))
    )
    (net (code "25") (name "ETXD0") (class "Default")
      (node (ref "IC4") (pin "3") (pinfunction "TXD_0_3") (pintype "bidirectional"))
      (node (ref "U$5") (pin "2") (pinfunction "AN16/ETXD0/PMD6/RE6_2") (pintype "bidirectional"))
    )
    (net (code "26") (name "ETXD1") (class "Default")
      (node (ref "IC4") (pin "4") (pinfunction "TXD_1_4") (pintype "bidirectional"))
      (node (ref "U$5") (pin "3") (pinfunction "AN15/ETXD1/PMD7/RE7_3") (pintype "bidirectional"))
    )
    (net (code "27") (name "ETXEN") (class "Default")
      (node (ref "IC4") (pin "2") (pinfunction "TX_EN_2") (pintype "bidirectional"))
      (node (ref "U$5") (pin "1") (pinfunction "AN17/ETXEN/RPE5/PMD5/RE5_1") (pintype "bidirectional"))
    )
    (net (code "28") (name "FLASH_CS") (class "Default")
      (node (ref "R13") (pin "1") (pinfunction "1_1") (pintype "passive"))
      (node (ref "U$2") (pin "1") (pinfunction "~{CE}_1") (pintype "bidirectional"))
      (node (ref "U$5") (pin "11") (pinfunction "AN45/C1INA/RPB5/RB5_11") (pintype "bidirectional"))
    )
    (net (code "29") (name "GND") (class "Default")
      (node (ref "C1") (pin "2") (pinfunction "2_2") (pintype "passive"))
      (node (ref "C10") (pin "2") (pinfunction "2_2") (pintype "passive"))
      (node (ref "C11") (pin "2") (pinfunction "2_2") (pintype "passive"))
      (node (ref "C12") (pin "-") (pinfunction "-_-") (pintype "passive"))
      (node (ref "C13") (pin "2") (pinfunction "2_2") (pintype "passive"))
      (node (ref "C14") (pin "2") (pinfunction "2_2") (pintype "passive"))
      (node (ref "C15") (pin "-") (pinfunction "-_-") (pintype "passive"))
      (node (ref "C16") (pin "2") (pinfunction "2_2") (pintype "passive"))
      (node (ref "C17") (pin "2") (pinfunction "2_2") (pintype "passive"))
      (node (ref "C18") (pin "2") (pinfunction "2_2") (pintype "passive"))
      (node (ref "C19") (pin "2") (pinfunction "2_2") (pintype "passive"))
      (node (ref "C2") (pin "2") (pinfunction "2_2") (pintype "passive"))
      (node (ref "C21") (pin "2") (pinfunction "2_2") (pintype "passive"))
      (node (ref "C22") (pin "2") (pinfunction "2_2") (pintype "passive"))
      (node (ref "C24") (pin "2") (pinfunction "2_2") (pintype "passive"))
      (node (ref "C25") (pin "2") (pinfunction "2_2") (pintype "passive"))
      (node (ref "C26") (pin "-") (pinfunction "-_-") (pintype "passive"))
      (node (ref "C27") (pin "2") (pinfunction "2_2") (pintype "passive"))
      (node (ref "C28") (pin "2") (pinfunction "2_2") (pintype "passive"))
      (node (ref "C29") (pin "2") (pinfunction "2_2") (pintype "passive"))
      (node (ref "C30") (pin "-") (pinfunction "-_-") (pintype "passive"))
      (node (ref "C31") (pin "2") (pinfunction "2_2") (pintype "passive"))
      (node (ref "C32") (pin "2") (pinfunction "2_2") (pintype "passive"))
      (node (ref "C38") (pin "2") (pinfunction "2_2") (pintype "passive"))
      (node (ref "C4") (pin "2") (pinfunction "2_2") (pintype "passive"))
      (node (ref "C40") (pin "2") (pinfunction "2_2") (pintype "passive"))
      (node (ref "C41") (pin "2") (pinfunction "2_2") (pintype "passive"))
      (node (ref "C42") (pin "2") (pinfunction "2_2") (pintype "passive"))
      (node (ref "C45") (pin "2") (pinfunction "2_2") (pintype "passive"))
      (node (ref "C46") (pin "2") (pinfunction "2_2") (pintype "passive"))
      (node (ref "C47") (pin "2") (pinfunction "2_2") (pintype "passive"))
      (node (ref "C48") (pin "2") (pinfunction "2_2") (pintype "passive"))
      (node (ref "C49") (pin "2") (pinfunction "2_2") (pintype "passive"))
      (node (ref "C50") (pin "2") (pinfunction "2_2") (pintype "passive"))
      (node (ref "C51") (pin "-") (pinfunction "-_-") (pintype "passive"))
      (node (ref "C52") (pin "-") (pinfunction "-_-") (pintype "passive"))
      (node (ref "C53") (pin "2") (pinfunction "2_2") (pintype "passive"))
      (node (ref "C54") (pin "2") (pinfunction "2_2") (pintype "passive"))
      (node (ref "C55") (pin "2") (pinfunction "2_2") (pintype "passive"))
      (node (ref "C56") (pin "2") (pinfunction "2_2") (pintype "passive"))
      (node (ref "C57") (pin "2") (pinfunction "2_2") (pintype "passive"))
      (node (ref "C59") (pin "2") (pinfunction "2_2") (pintype "passive"))
      (node (ref "C6") (pin "2") (pinfunction "2_2") (pintype "passive"))
      (node (ref "C7") (pin "2") (pinfunction "2_2") (pintype "passive"))
      (node (ref "C8") (pin "2") (pinfunction "2_2") (pintype "passive"))
      (node (ref "C9") (pin "2") (pinfunction "2_2") (pintype "passive"))
      (node (ref "IC1") (pin "2") (pinfunction "GND_2") (pintype "bidirectional"))
      (node (ref "IC2") (pin "1") (pinfunction "GND_1") (pintype "input"))
      (node (ref "IC4") (pin "15") (pinfunction "CDVSS_15") (pintype "power_in"))
      (node (ref "IC4") (pin "19") (pinfunction "ANA18VSS_19") (pintype "power_in"))
      (node (ref "IC4") (pin "35") (pinfunction "IO_VSS2_35") (pintype "power_in"))
      (node (ref "IC4") (pin "36") (pinfunction "CORE_VSS_36") (pintype "power_in"))
      (node (ref "IC4") (pin "47") (pinfunction "IO_VSS1_47") (pintype "power_in"))
      (node (ref "IC4") (pin "6") (pinfunction "TXD_3_6") (pintype "bidirectional"))
      (node (ref "IC5") (pin "1") (pinfunction "GND_1") (pintype "input"))
      (node (ref "JP1") (pin "1") (pinfunction "1_1") (pintype "passive"))
      (node (ref "JP2") (pin "3") (pinfunction "3_3") (pintype "passive"))
      (node (ref "JP3") (pin "1") (pinfunction "1_1") (pintype "passive"))
      (node (ref "JP5") (pin "GND1") (pinfunction "GND_GND1") (pintype "bidirectional"))
      (node (ref "R21") (pin "1") (pinfunction "1_1") (pintype "passive"))
      (node (ref "R26") (pin "2") (pinfunction "2_2") (pintype "passive"))
      (node (ref "R27") (pin "2") (pinfunction "2_2") (pintype "passive"))
      (node (ref "R28") (pin "2") (pinfunction "2_2") (pintype "passive"))
      (node (ref "R29") (pin "2") (pinfunction "2_2") (pintype "passive"))
      (node (ref "R36") (pin "2") (pinfunction "2_2") (pintype "passive"))
      (node (ref "R6") (pin "2") (pinfunction "2_2") (pintype "passive"))
      (node (ref "RJ1") (pin "GND") (pinfunction "GND_GND") (pintype "bidirectional"))
      (node (ref "RJ1") (pin "SHIELD0") (pinfunction "SHIELD0_SHIELD0") (pintype "bidirectional"))
      (node (ref "RJ1") (pin "SHIELD1") (pinfunction "SHIELD1_SHIELD1") (pintype "bidirectional"))
      (node (ref "U$1") (pin "2") (pinfunction "GND_2") (pintype "power_in"))
      (node (ref "U$2") (pin "4") (pinfunction "VSS_4") (pintype "bidirectional"))
      (node (ref "U$5") (pin "20") (pinfunction "AVSS_20") (pintype "bidirectional"))
      (node (ref "U$5") (pin "25") (pinfunction "VSS_25") (pintype "bidirectional"))
      (node (ref "U$5") (pin "35") (pinfunction "VSS_35") (pintype "bidirectional"))
      (node (ref "U$5") (pin "40") (pinfunction "VSS_40") (pintype "bidirectional"))
      (node (ref "U$5") (pin "55") (pinfunction "VSS_55") (pintype "bidirectional"))
      (node (ref "U$5") (pin "59") (pinfunction "VSS_59") (pintype "bidirectional"))
      (node (ref "U$5") (pin "7") (pinfunction "VSS_7") (pintype "bidirectional"))
      (node (ref "U$7") (pin "2") (pinfunction "GND_2") (pintype "power_in"))
      (node (ref "U1") (pin "6") (pinfunction "GND_6") (pintype "bidirectional"))
      (node (ref "U1") (pin "CD2") (pinfunction "SHIELD_CD2") (pintype "bidirectional"))
      (node (ref "U1") (pin "GND1") (pinfunction "SHIELD_GND1") (pintype "bidirectional"))
      (node (ref "U1") (pin "GND2") (pinfunction "SHIELD_GND2") (pintype "bidirectional"))
      (node (ref "U2") (pin "16") (pinfunction "DGND1_16") (pintype "power_in"))
      (node (ref "U2") (pin "20") (pinfunction "DGND2_20") (pintype "power_in"))
      (node (ref "U2") (pin "21") (pinfunction "DGND3_21") (pintype "power_in"))
      (node (ref "U2") (pin "22") (pinfunction "DGND4_22") (pintype "power_in"))
      (node (ref "U2") (pin "4") (pinfunction "DGND_4") (pintype "power_in"))
      (node (ref "X1") (pin "2") (pinfunction "S_2") (pintype "passive"))
      (node (ref "X2") (pin "1") (pinfunction "S_1") (pintype "passive"))
      (node (ref "X3") (pin "4") (pinfunction "4_4") (pintype "passive"))
      (node (ref "X3") (pin "M1") (pinfunction "S1_M1") (pintype "passive"))
      (node (ref "X3") (pin "M2") (pinfunction "S2_M2") (pintype "passive"))
      (node (ref "Y3") (pin "2") (pinfunction "3_2") (pintype "passive"))
      (node (ref "Y3") (pin "4") (pinfunction "3_4") (pintype "passive"))
    )
    (net (code "30") (name "LED_ACT") (class "Default")
      (node (ref "IC4") (pin "26") (pinfunction "LED_ACTCOL_26") (pintype "bidirectional"))
      (node (ref "RJ1") (pin "G-") (pinfunction "G-_G-") (pintype "bidirectional"))
    )
    (net (code "31") (name "LED_LINK") (class "Default")
      (node (ref "IC4") (pin "28") (pinfunction "LED_LNK_28") (pintype "bidirectional"))
      (node (ref "RJ1") (pin "Y-") (pinfunction "Y-_Y-") (pintype "bidirectional"))
    )
    (net (code "32") (name "MCLR") (class "Default")
      (node (ref "JP2") (pin "1") (pinfunction "1_1") (pintype "passive"))
      (node (ref "R12") (pin "1") (pinfunction "1_1") (pintype "passive"))
      (node (ref "U$5") (pin "9") (pinfunction "~{MCLR}_9") (pintype "bidirectional"))
    )
    (net (code "33") (name "MISO") (class "Default")
      (node (ref "R16") (pin "1") (pinfunction "1_1") (pintype "passive"))
      (node (ref "U$2") (pin "2") (pinfunction "SO_2") (pintype "bidirectional"))
      (node (ref "U$5") (pin "5") (pinfunction "AN13/C1INC/RPG7/SDA4/PMA4/RG7_5") (pintype "bidirectional"))
      (node (ref "U1") (pin "7") (pinfunction "DO_7") (pintype "bidirectional"))
    )
    (net (code "34") (name "MOSI") (class "Default")
      (node (ref "R14") (pin "2") (pinfunction "2_2") (pintype "passive"))
      (node (ref "U$2") (pin "5") (pinfunction "SI_5") (pintype "bidirectional"))
      (node (ref "U1") (pin "3") (pinfunction "DI_3") (pintype "bidirectional"))
    )
    (net (code "35") (name "Net-(C28-Pad1)") (class "Default")
      (node (ref "C28") (pin "1") (pinfunction "1_1") (pintype "passive"))
      (node (ref "R12") (pin "2") (pinfunction "2_2") (pintype "passive"))
      (node (ref "R9") (pin "1") (pinfunction "1_1") (pintype "passive"))
    )
    (net (code "36") (name "Net-(C36-Pad2)") (class "Default")
      (node (ref "C36") (pin "2") (pinfunction "2_2") (pintype "passive"))
      (node (ref "R23") (pin "1") (pinfunction "1_1") (pintype "passive"))
    )
    (net (code "37") (name "Net-(C37-Pad2)") (class "Default")
      (node (ref "C37") (pin "2") (pinfunction "2_2") (pintype "passive"))
      (node (ref "R24") (pin "1") (pinfunction "1_1") (pintype "passive"))
    )
    (net (code "38") (name "Net-(C39-Pad2)") (class "Default")
      (node (ref "C39") (pin "2") (pinfunction "2_2") (pintype "passive"))
      (node (ref "R22") (pin "1") (pinfunction "1_1") (pintype "passive"))
    )
    (net (code "39") (name "Net-(C43-Pad1)") (class "Default")
      (node (ref "C43") (pin "1") (pinfunction "1_1") (pintype "passive"))
      (node (ref "R31") (pin "1") (pinfunction "1_1") (pintype "passive"))
    )
    (net (code "40") (name "Net-(C43-Pad2)") (class "Default")
      (node (ref "C43") (pin "2") (pinfunction "2_2") (pintype "passive"))
      (node (ref "J1") (pin "TIP") (pinfunction "TIP_TIP") (pintype "bidirectional"))
      (node (ref "R34") (pin "1") (pinfunction "1_1") (pintype "passive"))
    )
    (net (code "41") (name "Net-(C44-Pad1)") (class "Default")
      (node (ref "C44") (pin "1") (pinfunction "1_1") (pintype "passive"))
      (node (ref "R32") (pin "1") (pinfunction "1_1") (pintype "passive"))
    )
    (net (code "42") (name "Net-(C44-Pad2)") (class "Default")
      (node (ref "C44") (pin "2") (pinfunction "2_2") (pintype "passive"))
      (node (ref "J1") (pin "RING1") (pinfunction "RING1_RING1") (pintype "bidirectional"))
      (node (ref "R33") (pin "1") (pinfunction "1_1") (pintype "passive"))
    )
    (net (code "43") (name "Net-(IC1-I{slash}O_1)") (class "Default")
      (node (ref "IC1") (pin "1") (pinfunction "I/O_1_1") (pintype "bidirectional"))
      (node (ref "X3") (pin "2") (pinfunction "2_2") (pintype "passive"))
    )
    (net (code "44") (name "Net-(IC1-I{slash}O_2)") (class "Default")
      (node (ref "IC1") (pin "3") (pinfunction "I/O_2_3") (pintype "bidirectional"))
      (node (ref "X3") (pin "3") (pinfunction "3_3") (pintype "passive"))
    )
    (net (code "45") (name "Net-(IC4-IP_PH_M)") (class "Default")
      (node (ref "IC4") (pin "20") (pinfunction "IP_PH_M_20") (pintype "input"))
      (node (ref "R10") (pin "1") (pinfunction "1_1") (pintype "passive"))
    )
    (net (code "46") (name "Net-(IC4-IP_PH_P)") (class "Default")
      (node (ref "IC4") (pin "21") (pinfunction "IP_PH_P_21") (pintype "input"))
      (node (ref "R7") (pin "1") (pinfunction "1_1") (pintype "passive"))
    )
    (net (code "47") (name "Net-(IC4-RX_DV)") (class "Default")
      (node (ref "IC4") (pin "39") (pinfunction "RX_DV_39") (pintype "bidirectional"))
      (node (ref "R20") (pin "2") (pinfunction "2_2") (pintype "passive"))
    )
    (net (code "48") (name "Net-(IC4-VREF)") (class "Default")
      (node (ref "IC4") (pin "24") (pinfunction "VREF_24") (pintype "bidirectional"))
      (node (ref "R6") (pin "1") (pinfunction "1_1") (pintype "passive"))
    )
    (net (code "49") (name "Net-(JP5-VCC)") (class "Default")
      (node (ref "F1") (pin "1") (pinfunction "1_1") (pintype "passive"))
      (node (ref "JP5") (pin "VBUS1") (pinfunction "VCC_VBUS1") (pintype "bidirectional"))
      (node (ref "X1") (pin "1") (pinfunction "S_1") (pintype "passive"))
    )
    (net (code "50") (name "Net-(R42-Pad2)") (class "Default")
      (node (ref "R42") (pin "2") (pinfunction "2_2") (pintype "passive"))
      (node (ref "RJ1") (pin "G+") (pinfunction "G+_G+") (pintype "bidirectional"))
    )
    (net (code "51") (name "Net-(R43-Pad1)") (class "Default")
      (node (ref "R43") (pin "1") (pinfunction "1_1") (pintype "passive"))
      (node (ref "RJ1") (pin "Y+") (pinfunction "Y+_Y+") (pintype "bidirectional"))
    )
    (net (code "52") (name "Net-(U$5-AN12{slash}C2IND{slash}RPG8{slash}SCL4{slash}PMA3{slash}RG8)") (class "Default")
      (node (ref "R14") (pin "1") (pinfunction "1_1") (pintype "passive"))
      (node (ref "U$5") (pin "6") (pinfunction "AN12/C2IND/RPG8/SCL4/PMA3/RG8_6") (pintype "bidirectional"))
    )
    (net (code "53") (name "Net-(U2A-GBUF)") (class "Default")
      (node (ref "R23") (pin "2") (pinfunction "2_2") (pintype "passive"))
      (node (ref "U2") (pin "42") (pinfunction "GBUF_42") (pintype "bidirectional"))
    )
    (net (code "54") (name "Net-(U2A-GPIO0)") (class "Default")
      (node (ref "R26") (pin "1") (pinfunction "1_1") (pintype "passive"))
      (node (ref "U2") (pin "33") (pinfunction "GPIO0_33") (pintype "bidirectional"))
    )
    (net (code "55") (name "Net-(U2A-GPIO1)") (class "Default")
      (node (ref "R27") (pin "1") (pinfunction "1_1") (pintype "passive"))
      (node (ref "U2") (pin "34") (pinfunction "GPIO1_34") (pintype "bidirectional"))
    )
    (net (code "56") (name "Net-(U2A-GPIO2{slash}DCLK)") (class "Default")
      (node (ref "R28") (pin "1") (pinfunction "1_1") (pintype "passive"))
      (node (ref "U2") (pin "9") (pinfunction "GPIO2/DCLK_9") (pintype "bidirectional"))
    )
    (net (code "57") (name "Net-(U2A-GPIO3{slash}SDATA)") (class "Default")
      (node (ref "R29") (pin "1") (pinfunction "1_1") (pintype "passive"))
      (node (ref "U2") (pin "10") (pinfunction "GPIO3/SDATA_10") (pintype "bidirectional"))
    )
    (net (code "58") (name "Net-(U2A-LEFT)") (class "Default")
      (node (ref "R22") (pin "2") (pinfunction "2_2") (pintype "passive"))
      (node (ref "R31") (pin "2") (pinfunction "2_2") (pintype "passive"))
      (node (ref "U2") (pin "46") (pinfunction "LEFT_46") (pintype "bidirectional"))
    )
    (net (code "59") (name "Net-(U2A-RCAP)") (class "Default")
      (node (ref "R25") (pin "2") (pinfunction "2_2") (pintype "passive"))
      (node (ref "U2") (pin "44") (pinfunction "RCAP_44") (pintype "bidirectional"))
    )
    (net (code "60") (name "Net-(U2A-RIGHT)") (class "Default")
      (node (ref "R24") (pin "2") (pinfunction "2_2") (pintype "passive"))
      (node (ref "R32") (pin "2") (pinfunction "2_2") (pintype "passive"))
      (node (ref "U2") (pin "39") (pinfunction "RIGHT_39") (pintype "bidirectional"))
    )
    (net (code "61") (name "Net-(U2A-RX)") (class "Default")
      (node (ref "R30") (pin "1") (pinfunction "1_1") (pintype "passive"))
      (node (ref "U2") (pin "26") (pinfunction "RX_26") (pintype "bidirectional"))
    )
    (net (code "62") (name "Net-(U2A-XTALI)") (class "Default")
      (node (ref "C50") (pin "1") (pinfunction "1_1") (pintype "passive"))
      (node (ref "R35") (pin "2") (pinfunction "2_2") (pintype "passive"))
      (node (ref "U2") (pin "18") (pinfunction "XTALI_18") (pintype "bidirectional"))
      (node (ref "Y3") (pin "1") (pinfunction "2_1") (pintype "passive"))
    )
    (net (code "63") (name "Net-(U2A-XTALO)") (class "Default")
      (node (ref "C49") (pin "1") (pinfunction "1_1") (pintype "passive"))
      (node (ref "R35") (pin "1") (pinfunction "1_1") (pintype "passive"))
      (node (ref "U2") (pin "17") (pinfunction "XTALO_17") (pintype "bidirectional"))
      (node (ref "Y3") (pin "3") (pinfunction "1_3") (pintype "passive"))
    )
    (net (code "64") (name "PGEC") (class "Default")
      (node (ref "JP2") (pin "5") (pinfunction "5_5") (pintype "passive"))
      (node (ref "U$5") (pin "15") (pinfunction "PGEC1/VREF-/CVREF-/AN1/RPB1/RB1_15") (pintype "bidirectional"))
    )
    (net (code "65") (name "PGED") (class "Default")
      (node (ref "JP2") (pin "4") (pinfunction "4_4") (pintype "passive"))
      (node (ref "U$5") (pin "16") (pinfunction "PGED1/VREF+/CVREF+/AN0/RPB0/PMA6/RB0_16") (pintype "bidirectional"))
    )
    (net (code "66") (name "PH0") (class "Default")
      (node (ref "U$1") (pin "3") (pinfunction "OUT_3") (pintype "output"))
      (node (ref "U$5") (pin "31") (pinfunction "OSC1/CLKI/RC12_31") (pintype "bidirectional"))
    )
    (net (code "67") (name "RD_N") (class "Default")
      (node (ref "IC4") (pin "13") (pinfunction "TPRDM_13") (pintype "bidirectional"))
      (node (ref "R5") (pin "1") (pinfunction "1_1") (pintype "passive"))
      (node (ref "RJ1") (pin "RD-") (pinfunction "RD-_RD-") (pintype "bidirectional"))
    )
    (net (code "68") (name "RD_P") (class "Default")
      (node (ref "IC4") (pin "14") (pinfunction "TPRDP_14") (pintype "bidirectional"))
      (node (ref "R4") (pin "1") (pinfunction "1_1") (pintype "passive"))
      (node (ref "RJ1") (pin "RD+") (pinfunction "RD+_RD+") (pintype "bidirectional"))
    )
    (net (code "69") (name "REG_OUT") (class "Default")
      (node (ref "C18") (pin "1") (pinfunction "1_1") (pintype "passive"))
      (node (ref "C19") (pin "1") (pinfunction "1_1") (pintype "passive"))
      (node (ref "C24") (pin "1") (pinfunction "1_1") (pintype "passive"))
      (node (ref "C32") (pin "1") (pinfunction "1_1") (pintype "passive"))
      (node (ref "IC4") (pin "18") (pinfunction "ANA18VDD_18") (pintype "power_in"))
      (node (ref "IC4") (pin "23") (pinfunction "REG_OUT_23") (pintype "output"))
      (node (ref "IC4") (pin "37") (pinfunction "CORE_VDD_37") (pintype "power_in"))
    )
    (net (code "70") (name "SCK") (class "Default")
      (node (ref "U$2") (pin "6") (pinfunction "SCK_6") (pintype "bidirectional"))
      (node (ref "U$5") (pin "4") (pinfunction "AN14/C1IND/RPG6/SCK2/PMA5/RG6_4") (pintype "bidirectional"))
      (node (ref "U1") (pin "5") (pinfunction "SCK_5") (pintype "bidirectional"))
    )
    (net (code "71") (name "SD_CS") (class "Default")
      (node (ref "R11") (pin "1") (pinfunction "1_1") (pintype "passive"))
      (node (ref "U$5") (pin "14") (pinfunction "AN2/C2INB/RPB2/RB2_14") (pintype "bidirectional"))
      (node (ref "U1") (pin "2") (pinfunction "CS_2") (pintype "bidirectional"))
    )
    (net (code "72") (name "SD_PRESENT") (class "Default")
      (node (ref "R8") (pin "1") (pinfunction "1_1") (pintype "passive"))
      (node (ref "U$5") (pin "10") (pinfunction "AN11/C2INC/RPG9/PMA2/RG9_10") (pintype "bidirectional"))
      (node (ref "U1") (pin "CD1") (pinfunction "SHIELD_CD1") (pintype "bidirectional"))
    )
    (net (code "73") (name "TD_N") (class "Default")
      (node (ref "IC4") (pin "16") (pinfunction "TPTDM_16") (pintype "bidirectional"))
      (node (ref "R3") (pin "1") (pinfunction "1_1") (pintype "passive"))
      (node (ref "RJ1") (pin "TD-") (pinfunction "TD-_TD-") (pintype "bidirectional"))
    )
    (net (code "74") (name "TD_P") (class "Default")
      (node (ref "IC4") (pin "17") (pinfunction "TPTDP_17") (pintype "bidirectional"))
      (node (ref "R2") (pin "1") (pinfunction "1_1") (pintype "passive"))
      (node (ref "RJ1") (pin "TD+") (pinfunction "TD+_TD+") (pintype "bidirectional"))
    )
    (net (code "75") (name "U1_RX") (class "Default")
      (node (ref "JP3") (pin "3") (pinfunction "3_3") (pintype "passive"))
      (node (ref "U$5") (pin "50") (pinfunction "ETXERR/AETXEN/RPD2/SDA3/RD2_50") (pintype "bidirectional"))
    )
    (net (code "76") (name "U1_TX") (class "Default")
      (node (ref "JP3") (pin "2") (pinfunction "2_2") (pintype "passive"))
      (node (ref "U$5") (pin "51") (pinfunction "AERXERR/ETXCLK/RPD3/SCL3/RD3_51") (pintype "bidirectional"))
    )
    (net (code "77") (name "VBUS") (class "Default")
      (node (ref "C12") (pin "+") (pinfunction "+_+") (pintype "passive"))
      (node (ref "C13") (pin "1") (pinfunction "1_1") (pintype "passive"))
      (node (ref "C27") (pin "1") (pinfunction "1_1") (pintype "passive"))
      (node (ref "C30") (pin "+") (pinfunction "+_+") (pintype "passive"))
      (node (ref "C52") (pin "+") (pinfunction "+_+") (pintype "passive"))
      (node (ref "C53") (pin "1") (pinfunction "1_1") (pintype "passive"))
      (node (ref "F1") (pin "2") (pinfunction "2_2") (pintype "passive"))
      (node (ref "IC1") (pin "5") (pinfunction "VBUS_5") (pintype "bidirectional"))
      (node (ref "IC2") (pin "3") (pinfunction "IN_3") (pintype "input"))
      (node (ref "IC5") (pin "3") (pinfunction "IN_3") (pintype "input"))
      (node (ref "U$5") (pin "33") (pinfunction "VBUS_33") (pintype "bidirectional"))
      (node (ref "X3") (pin "1") (pinfunction "1_1") (pintype "passive"))
    )
    (net (code "78") (name "VS_AGND") (class "Default")
      (node (ref "C33") (pin "2") (pinfunction "2_2") (pintype "passive"))
      (node (ref "C34") (pin "2") (pinfunction "2_2") (pintype "passive"))
      (node (ref "C35") (pin "2") (pinfunction "2_2") (pintype "passive"))
      (node (ref "C36") (pin "1") (pinfunction "1_1") (pintype "passive"))
      (node (ref "C37") (pin "1") (pinfunction "1_1") (pintype "passive"))
      (node (ref "C39") (pin "1") (pinfunction "1_1") (pintype "passive"))
      (node (ref "C58") (pin "2") (pinfunction "2_2") (pintype "passive"))
      (node (ref "J1") (pin "EARTH") (pinfunction "EARTH_EARTH") (pintype "bidirectional"))
      (node (ref "R21") (pin "2") (pinfunction "2_2") (pintype "passive"))
      (node (ref "R25") (pin "1") (pinfunction "1_1") (pintype "passive"))
      (node (ref "R33") (pin "2") (pinfunction "2_2") (pintype "passive"))
      (node (ref "R34") (pin "2") (pinfunction "2_2") (pintype "passive"))
      (node (ref "U2") (pin "37") (pinfunction "AGND_37") (pintype "power_in"))
      (node (ref "U2") (pin "40") (pinfunction "AGND1_40") (pintype "power_in"))
      (node (ref "U2") (pin "41") (pinfunction "AGND2_41") (pintype "power_in"))
      (node (ref "U2") (pin "47") (pinfunction "AGND3_47") (pintype "power_in"))
    )
    (net (code "79") (name "VS_AVDD") (class "Default")
      (node (ref "C33") (pin "1") (pinfunction "1_1") (pintype "passive"))
      (node (ref "C34") (pin "1") (pinfunction "1_1") (pintype "passive"))
      (node (ref "C35") (pin "1") (pinfunction "1_1") (pintype "passive"))
      (node (ref "C58") (pin "1") (pinfunction "1_1") (pintype "passive"))
      (node (ref "L1") (pin "1") (pinfunction "1_1") (pintype "passive"))
      (node (ref "U2") (pin "38") (pinfunction "AVDD_38") (pintype "power_in"))
      (node (ref "U2") (pin "43") (pinfunction "AVDD1_43") (pintype "power_in"))
      (node (ref "U2") (pin "45") (pinfunction "AVDD2_45") (pintype "power_in"))
    )
    (net (code "80") (name "VS_CVDD") (class "Default")
      (node (ref "C45") (pin "1") (pinfunction "1_1") (pintype "passive"))
      (node (ref "C46") (pin "1") (pinfunction "1_1") (pintype "passive"))
      (node (ref "C47") (pin "1") (pinfunction "1_1") (pintype "passive"))
      (node (ref "C48") (pin "1") (pinfunction "1_1") (pintype "passive"))
      (node (ref "C57") (pin "1") (pinfunction "1_1") (pintype "passive"))
      (node (ref "L2") (pin "1") (pinfunction "1_1") (pintype "passive"))
      (node (ref "U2") (pin "24") (pinfunction "CVDD2_24") (pintype "power_in"))
      (node (ref "U2") (pin "31") (pinfunction "CVDD3_31") (pintype "power_in"))
      (node (ref "U2") (pin "5") (pinfunction "CVDD_5") (pintype "power_in"))
      (node (ref "U2") (pin "7") (pinfunction "CVDD1_7") (pintype "power_in"))
    )
    (net (code "81") (name "VS_DREQ") (class "Default")
      (node (ref "U$5") (pin "27") (pinfunction "TCK/AN7/PMA11/RB12_27") (pintype "bidirectional"))
      (node (ref "U2") (pin "8") (pinfunction "DREQ_8") (pintype "bidirectional"))
    )
    (net (code "82") (name "VS_MISO") (class "Default")
      (node (ref "U$5") (pin "22") (pinfunction "AN49/RPB9/PMA7/RB9_22") (pintype "bidirectional"))
      (node (ref "U2") (pin "30") (pinfunction "SO_30") (pintype "bidirectional"))
    )
    (net (code "83") (name "VS_MOSI") (class "Default")
      (node (ref "U$5") (pin "23") (pinfunction "TMS/CVREFOUT/AN5/RPB10/PMA13/RB10_23") (pintype "bidirectional"))
      (node (ref "U2") (pin "29") (pinfunction "SI_29") (pintype "bidirectional"))
    )
    (net (code "84") (name "VS_SCK") (class "Default")
      (node (ref "U$5") (pin "29") (pinfunction "AN9/RPB14/SCK3/PMA1/RB14_29") (pintype "bidirectional"))
      (node (ref "U2") (pin "28") (pinfunction "SCLK_28") (pintype "bidirectional"))
    )
    (net (code "85") (name "VS_XCS") (class "Default")
      (node (ref "U$5") (pin "24") (pinfunction "TDO/AN6/PMA12/RB11_24") (pintype "bidirectional"))
      (node (ref "U2") (pin "23") (pinfunction "XCS_23") (pintype "bidirectional"))
    )
    (net (code "86") (name "VS_XDCS") (class "Default")
      (node (ref "U$5") (pin "21") (pinfunction "AN48/RPB8/PMA10/RB8_21") (pintype "bidirectional"))
      (node (ref "U2") (pin "13") (pinfunction "XDCS/BSYNC_13") (pintype "bidirectional"))
    )
    (net (code "87") (name "VS_XRST") (class "Default")
      (node (ref "R36") (pin "1") (pinfunction "1_1") (pintype "passive"))
      (node (ref "U$5") (pin "28") (pinfunction "TDI/AN8/RB13_28") (pintype "bidirectional"))
      (node (ref "U2") (pin "3") (pinfunction "XRESET_3") (pintype "bidirectional"))
    )
    (net (code "88") (name "_2V6") (class "Default")
      (node (ref "C51") (pin "+") (pinfunction "+_+") (pintype "passive"))
      (node (ref "C54") (pin "1") (pinfunction "1_1") (pintype "passive"))
      (node (ref "IC5") (pin "2") (pinfunction "OUT_2") (pintype "passive"))
      (node (ref "IC5") (pin "TAB") (pinfunction "OUT1_TAB") (pintype "passive"))
      (node (ref "L1") (pin "2") (pinfunction "2_2") (pintype "passive"))
      (node (ref "L2") (pin "2") (pinfunction "2_2") (pintype "passive"))
    )
    (net (code "89") (name "unconnected-(IC4-CLK2MAC-Pad25)") (class "Default")
      (node (ref "IC4") (pin "25") (pinfunction "CLK2MAC_25") (pintype "bidirectional"))
    )
    (net (code "90") (name "unconnected-(IC4-COL-Pad42)") (class "Default")
      (node (ref "IC4") (pin "42") (pinfunction "COL_42") (pintype "bidirectional"))
    )
    (net (code "91") (name "unconnected-(IC4-LED_SPD-Pad27)") (class "Default")
      (node (ref "IC4") (pin "27") (pinfunction "LED_SPD_27") (pintype "bidirectional"))
    )
    (net (code "92") (name "unconnected-(IC4-RXD_2-Pad45)") (class "Default")
      (node (ref "IC4") (pin "45") (pinfunction "RXD_2_45") (pintype "bidirectional"))
    )
    (net (code "93") (name "unconnected-(IC4-RXD_3-Pad46)") (class "Default")
      (node (ref "IC4") (pin "46") (pinfunction "RXD_3_46") (pintype "bidirectional"))
    )
    (net (code "94") (name "unconnected-(IC4-RX_CLK-Pad38)") (class "Default")
      (node (ref "IC4") (pin "38") (pinfunction "RX_CLK_38") (pintype "bidirectional"))
    )
    (net (code "95") (name "unconnected-(IC4-TCK-Pad8)") (class "Default")
      (node (ref "IC4") (pin "8") (pinfunction "TCK_8") (pintype "input"))
    )
    (net (code "96") (name "unconnected-(IC4-TDI-Pad12)") (class "Default")
      (node (ref "IC4") (pin "12") (pinfunction "TDI_12") (pintype "input"))
    )
    (net (code "97") (name "unconnected-(IC4-TDO-Pad9)") (class "Default")
      (node (ref "IC4") (pin "9") (pinfunction "TDO_9") (pintype "output"))
    )
    (net (code "98") (name "unconnected-(IC4-TMS-Pad10)") (class "Default")
      (node (ref "IC4") (pin "10") (pinfunction "TMS_10") (pintype "input"))
    )
    (net (code "99") (name "unconnected-(IC4-TRST_N-Pad11)") (class "Default")
      (node (ref "IC4") (pin "11") (pinfunction "TRST_N_11") (pintype "input"))
    )
    (net (code "100") (name "unconnected-(IC4-TXD_2-Pad5)") (class "Default")
      (node (ref "IC4") (pin "5") (pinfunction "TXD_2_5") (pintype "bidirectional"))
    )
    (net (code "101") (name "unconnected-(IC4-TX_CLK-Pad1)") (class "Default")
      (node (ref "IC4") (pin "1") (pinfunction "TX_CLK_1") (pintype "bidirectional"))
    )
    (net (code "102") (name "unconnected-(IC4-X2-Pad33)") (class "Default")
      (node (ref "IC4") (pin "33") (pinfunction "X2_33") (pintype "output"))
    )
    (net (code "103") (name "unconnected-(J1-PadRING2)") (class "Default")
      (node (ref "J1") (pin "RING2") (pinfunction "RING2_RING2") (pintype "bidirectional"))
    )
    (net (code "104") (name "unconnected-(JP2-Pad2)") (class "Default")
      (node (ref "JP2") (pin "2") (pinfunction "2_2") (pintype "passive"))
    )
    (net (code "105") (name "unconnected-(JP2-Pad6)") (class "Default")
      (node (ref "JP2") (pin "6") (pinfunction "6_6") (pintype "passive"))
    )
    (net (code "106") (name "unconnected-(JP5-D+-PadD+1)") (class "Default")
      (node (ref "JP5") (pin "D+1") (pinfunction "D+_D+1") (pintype "bidirectional"))
    )
    (net (code "107") (name "unconnected-(JP5-D--PadD-1)") (class "Default")
      (node (ref "JP5") (pin "D-1") (pinfunction "D-_D-1") (pintype "bidirectional"))
    )
    (net (code "108") (name "unconnected-(JP5-ID-PadID1)") (class "Default")
      (node (ref "JP5") (pin "ID1") (pinfunction "ID_ID1") (pintype "bidirectional"))
    )
    (net (code "109") (name "unconnected-(RJ1-PadNC)") (class "Default")
      (node (ref "RJ1") (pin "NC") (pinfunction "NC_NC") (pintype "bidirectional"))
    )
    (net (code "110") (name "unconnected-(U$1-TRI-Pad1)") (class "Default")
      (node (ref "U$1") (pin "1") (pinfunction "TRI_1") (pintype "input"))
    )
    (net (code "111") (name "unconnected-(U$5-AERXCLK{slash}AEREFCLK{slash}ECRS{slash}RPD11{slash}PMCS1{slash}PMA14{slash}RD11-Pad45)") (class "Default")
      (node (ref "U$5") (pin "45") (pinfunction "AERXCLK/AEREFCLK/ECRS/RPD11/PMCS1/PMA14/RD11_45") (pintype "bidirectional"))
    )
    (net (code "112") (name "unconnected-(U$5-AERXD1{slash}ETXD3{slash}RPD0{slash}RTCC{slash}INT0{slash}RD0-Pad46)") (class "Default")
      (node (ref "U$5") (pin "46") (pinfunction "AERXD1/ETXD3/RPD0/RTCC/INT0/RD0_46") (pintype "bidirectional"))
    )
    (net (code "113") (name "unconnected-(U$5-ERXD3{slash}AETXD1{slash}RPF0{slash}RF0-Pad56)") (class "Default")
      (node (ref "U$5") (pin "56") (pinfunction "ERXD3/AETXD1/RPF0/RF0_56") (pintype "bidirectional"))
    )
    (net (code "114") (name "unconnected-(U$5-OSC2{slash}CLKO{slash}RC15-Pad32)") (class "Default")
      (node (ref "U$5") (pin "32") (pinfunction "OSC2/CLKO/RC15_32") (pintype "bidirectional"))
    )
    (net (code "115") (name "unconnected-(U$5-RPF3{slash}USBID{slash}RF3-Pad38)") (class "Default")
      (node (ref "U$5") (pin "38") (pinfunction "RPF3/USBID/RF3_38") (pintype "bidirectional"))
    )
    (net (code "116") (name "unconnected-(U$5-SQICS0{slash}RPD4{slash}PMWR{slash}RD4-Pad52)") (class "Default")
      (node (ref "U$5") (pin "52") (pinfunction "SQICS0/RPD4/PMWR/RD4_52") (pintype "bidirectional"))
    )
    (net (code "117") (name "unconnected-(U$5-SQICS1{slash}RPD5{slash}PMRD{slash}RD5-Pad53)") (class "Default")
      (node (ref "U$5") (pin "53") (pinfunction "SQICS1/RPD5/PMRD/RD5_53") (pintype "bidirectional"))
    )
    (net (code "118") (name "unconnected-(U$7-TRI-Pad1)") (class "Default")
      (node (ref "U$7") (pin "1") (pinfunction "TRI_1") (pintype "input"))
    )
    (net (code "119") (name "unconnected-(U1-NC-Pad1)") (class "Default")
      (node (ref "U1") (pin "1") (pinfunction "NC_1") (pintype "bidirectional"))
    )
    (net (code "120") (name "unconnected-(U1-RSV-Pad8)") (class "Default")
      (node (ref "U1") (pin "8") (pinfunction "RSV_8") (pintype "bidirectional"))
    )
    (net (code "121") (name "unconnected-(U2A-LINEIN-Pad48)") (class "Default")
      (node (ref "U2") (pin "48") (pinfunction "LINEIN_48") (pintype "bidirectional"))
    )
    (net (code "122") (name "unconnected-(U2A-MICN-Pad2)") (class "Default")
      (node (ref "U2") (pin "2") (pinfunction "MICN_2") (pintype "bidirectional"))
    )
    (net (code "123") (name "unconnected-(U2A-MICP-Pad1)") (class "Default")
      (node (ref "U2") (pin "1") (pinfunction "MICP_1") (pintype "bidirectional"))
    )
    (net (code "124") (name "unconnected-(U2A-TX-Pad27)") (class "Default")
      (node (ref "U2") (pin "27") (pinfunction "TX_27") (pintype "bidirectional"))
    )
    (net (code "125") (name "unconnected-(U2A-VCO-Pad15)") (class "Default")
      (node (ref "U2") (pin "15") (pinfunction "VCO_15") (pintype "bidirectional"))
    )
  )
)
